# Copy_of_Delay.net
KiCad netlist of a schematic drawn in Altium Designer
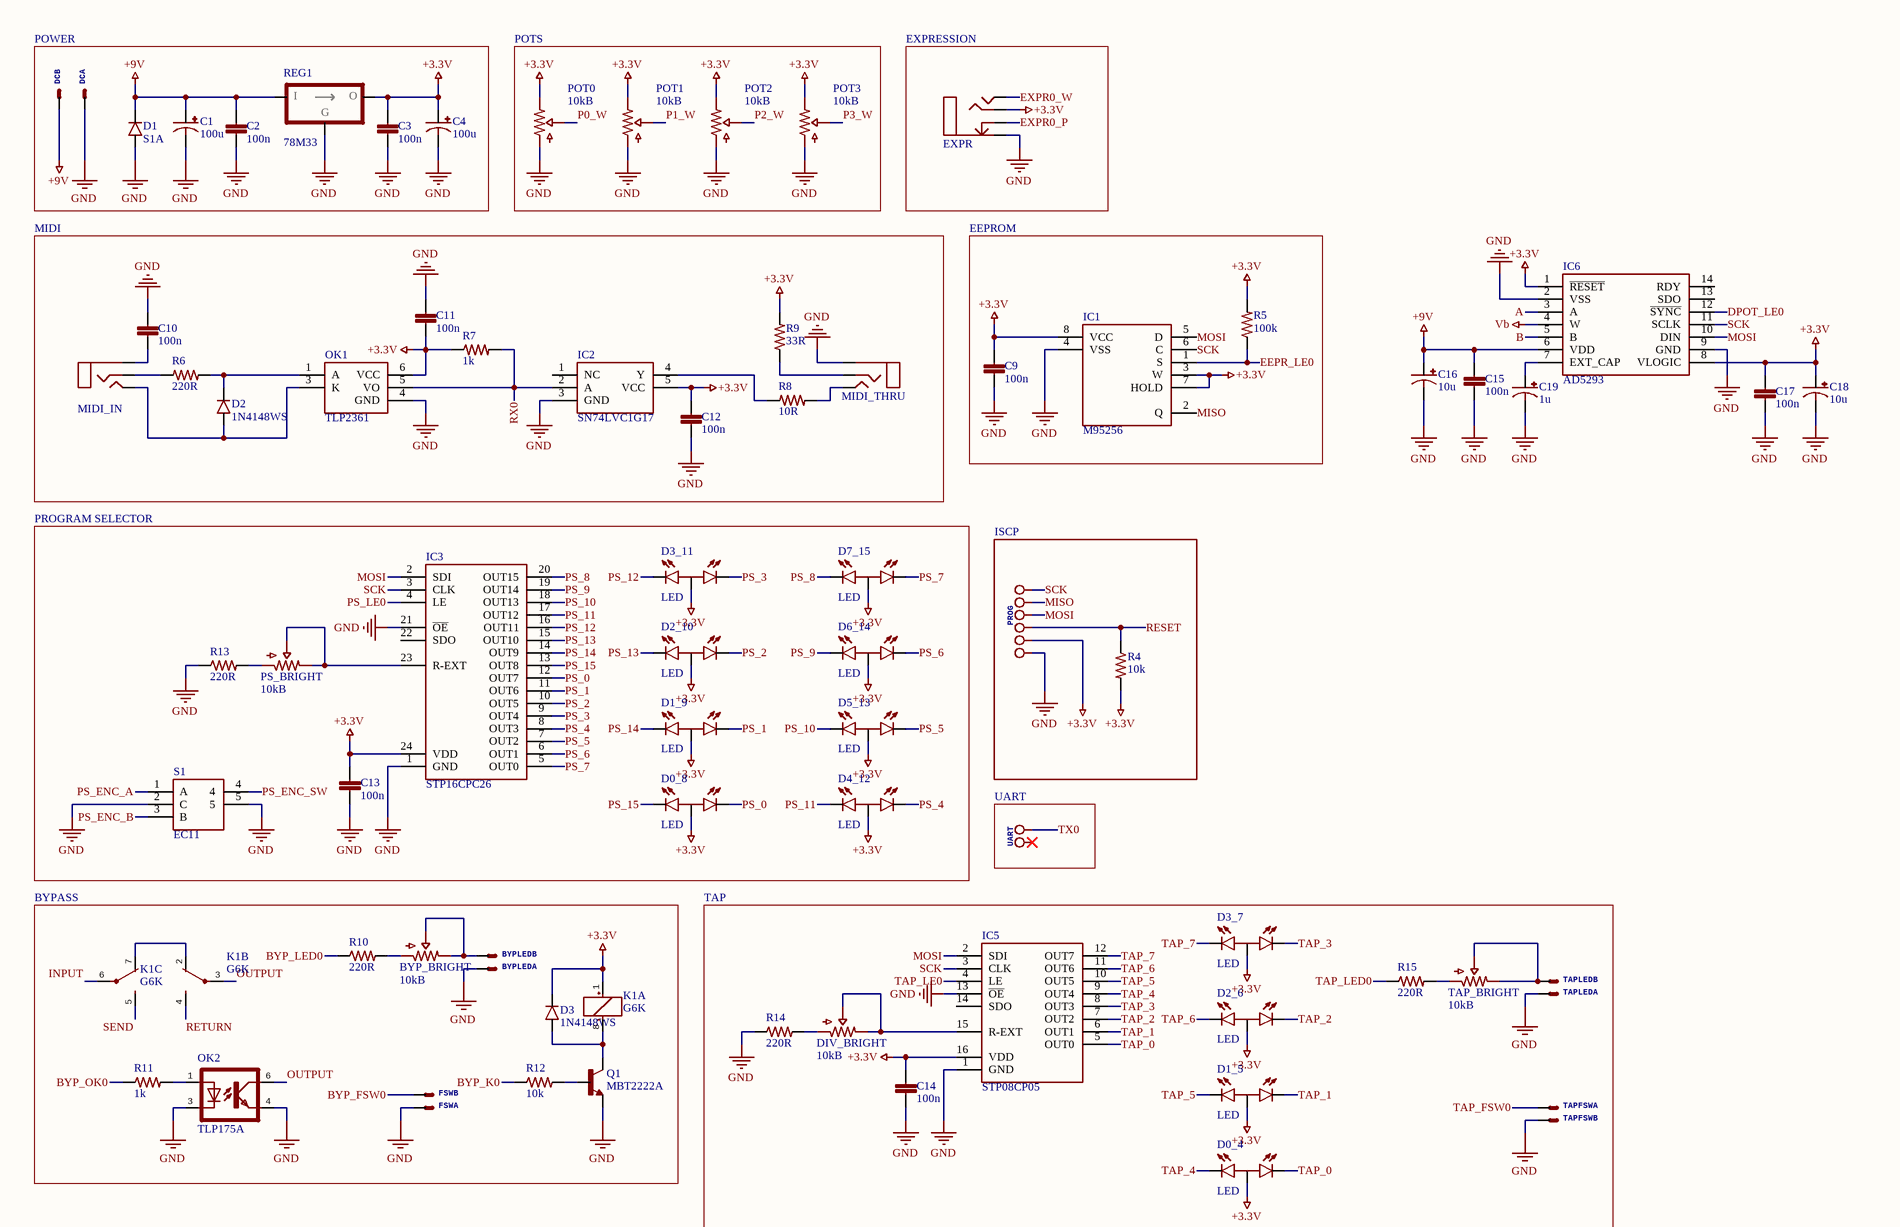
[diagram p0: Copy of Delay.SchDoc, top left]
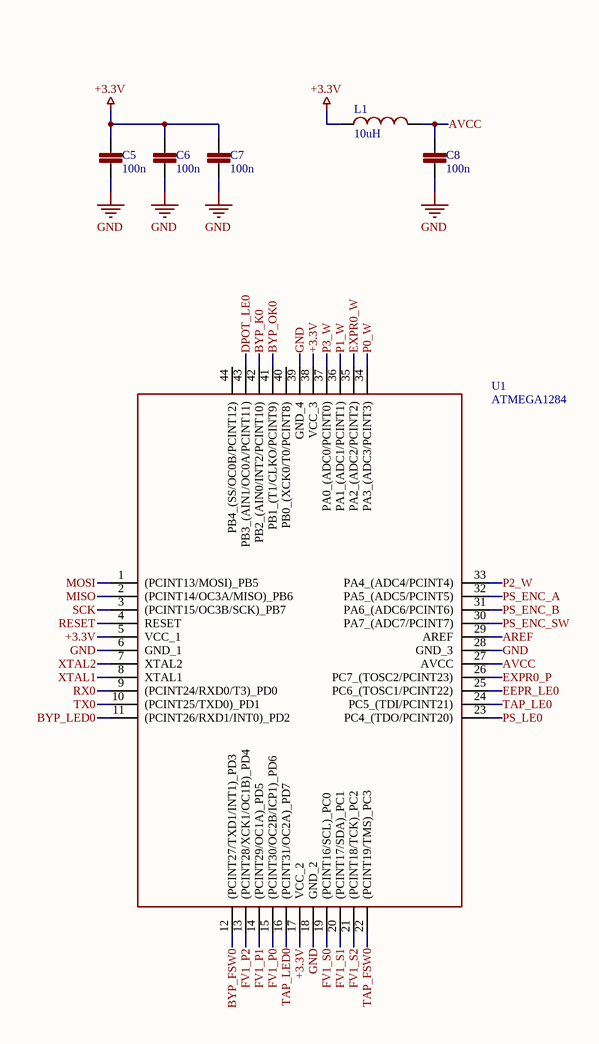
[diagram p1: Copy of Delay.SchDoc, top right]
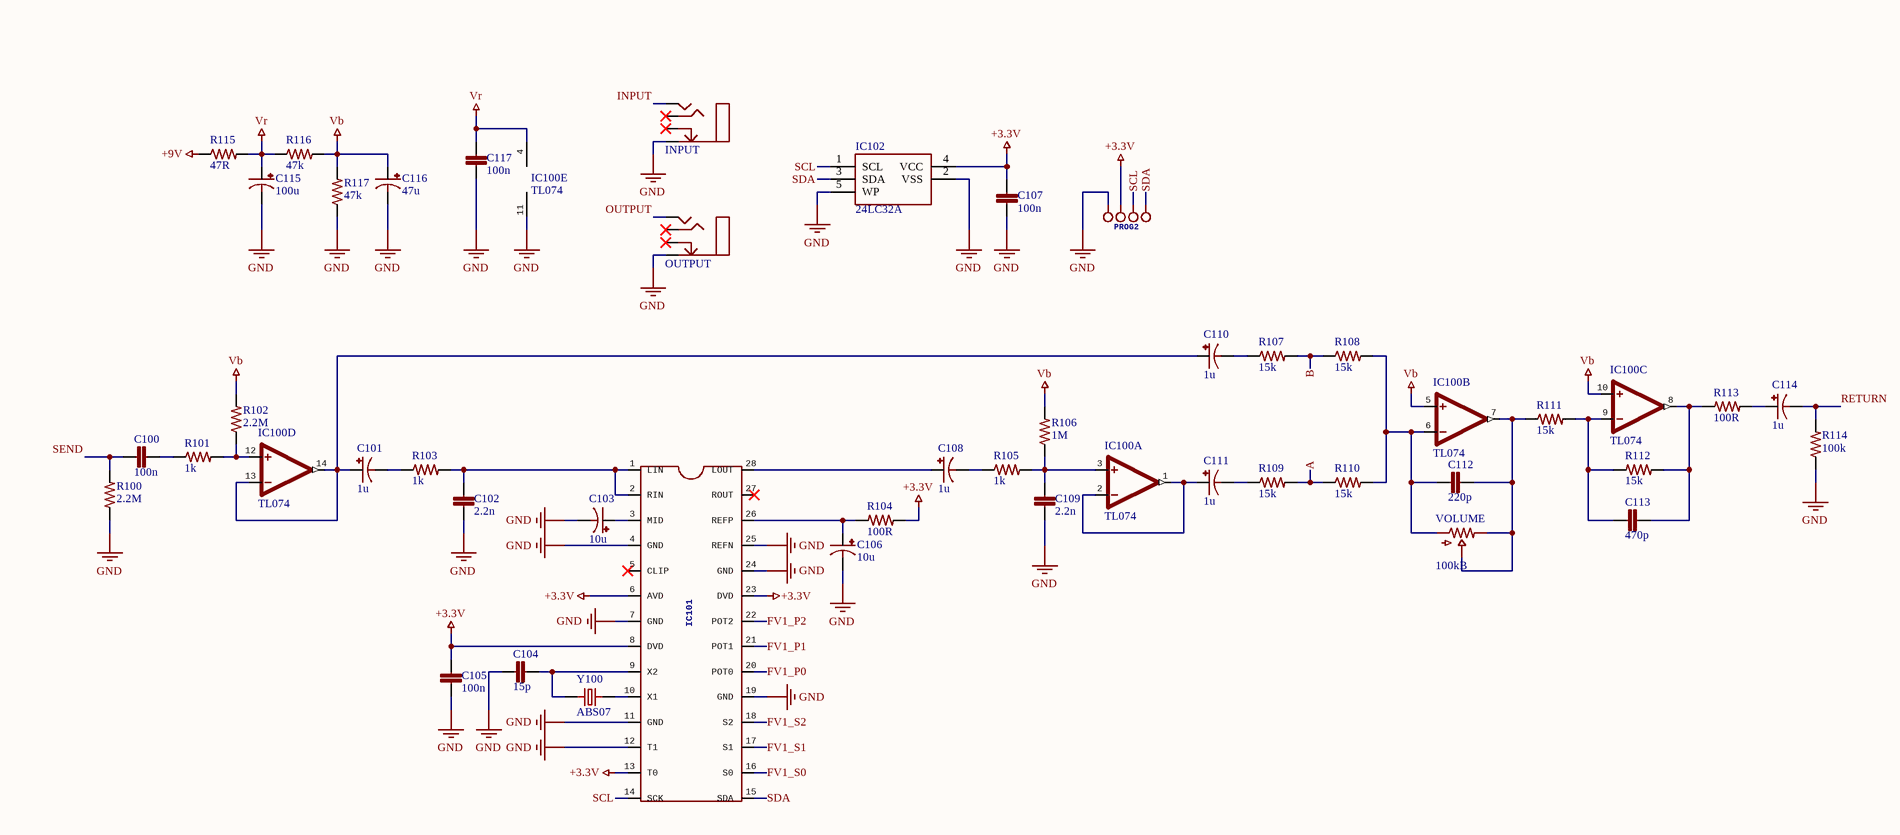
[diagram p2: Copy of Delay.SchDoc, bottom left]

(export (version "E")
  (design (tool "Eeschema 10.0.6"))
  (components
    (comp (ref "BYPLED")
      (value "~")
      (footprint "JST-XH-02")
      (description "2 Pins male XH header")
      (libsource (lib "Pedals") (part "JST-XH-02"))
    )
    (comp (ref "BYP_BRIGHT")
      (value "10kB")
      (footprint "BOURNS_3362P")
      (description "10k Lin 3362P trimmer")
      (libsource (lib "Pedals") (part "TRIM_10kB_3362P"))
    )
    (comp (ref "C1")
      (value "100u")
      (footprint "CAPAE_D")
      (description "CAP ALUM 100UF 25V SMD")
      (fields
        (field (name "MANUFACTURER") "Multicomp")
        (field (name "MANUFACTURER PART NUMBER") "MCVVT025M101EA6L")
      )
      (libsource (lib "Pedals SMD") (part "MCVVT025M101EA6L"))
    )
    (comp (ref "C2")
      (value "100n")
      (footprint "CHIP_0603")
      (description "CAP CER 100NF 50V X7R 0603")
      (fields
        (field (name "MANUFACTURER") "Multicomp")
        (field (name "MANUFACTURER PART NUMBER") "MC0603B104K500CT")
      )
      (libsource (lib "") (part "MC0603B104K500CT_2"))
    )
    (comp (ref "C3")
      (value "100n")
      (footprint "CHIP_0603")
      (description "CAP CER 100NF 50V X7R 0603")
      (fields
        (field (name "MANUFACTURER") "Multicomp")
        (field (name "MANUFACTURER PART NUMBER") "MC0603B104K500CT")
      )
      (libsource (lib "Pedals SMD") (part "MC0603B104K500CT"))
    )
    (comp (ref "C4")
      (value "100u")
      (footprint "CAPAE_D")
      (description "CAP ALUM 100UF 25V SMD")
      (fields
        (field (name "MANUFACTURER") "Multicomp")
        (field (name "MANUFACTURER PART NUMBER") "MCVVT025M101EA6L")
      )
      (libsource (lib "Pedals SMD") (part "MCVVT025M101EA6L"))
    )
    (comp (ref "C5")
      (value "100n")
      (footprint "CHIP_0603")
      (description "CAP CER 100NF 50V X7R 0603")
      (fields
        (field (name "MANUFACTURER") "Multicomp")
        (field (name "MANUFACTURER PART NUMBER") "MC0603B104K500CT")
      )
      (libsource (lib "Pedals SMD") (part "MC0603B104K500CT"))
    )
    (comp (ref "C6")
      (value "100n")
      (footprint "CHIP_0603")
      (description "CAP CER 100NF 50V X7R 0603")
      (fields
        (field (name "MANUFACTURER") "Multicomp")
        (field (name "MANUFACTURER PART NUMBER") "MC0603B104K500CT")
      )
      (libsource (lib "Pedals SMD") (part "MC0603B104K500CT"))
    )
    (comp (ref "C7")
      (value "100n")
      (footprint "CHIP_0603")
      (description "CAP CER 100NF 50V X7R 0603")
      (fields
        (field (name "MANUFACTURER") "Multicomp")
        (field (name "MANUFACTURER PART NUMBER") "MC0603B104K500CT")
      )
      (libsource (lib "Pedals SMD") (part "MC0603B104K500CT"))
    )
    (comp (ref "C8")
      (value "100n")
      (footprint "CHIP_0603")
      (description "CAP CER 100NF 50V X7R 0603")
      (fields
        (field (name "MANUFACTURER") "Multicomp")
        (field (name "MANUFACTURER PART NUMBER") "MC0603B104K500CT")
      )
      (libsource (lib "Pedals SMD") (part "MC0603B104K500CT"))
    )
    (comp (ref "C9")
      (value "100n")
      (footprint "CHIP_0603")
      (description "CAP CER 100NF 50V X7R 0603")
      (fields
        (field (name "MANUFACTURER") "Multicomp")
        (field (name "MANUFACTURER PART NUMBER") "MC0603B104K500CT")
      )
      (libsource (lib "") (part "MC0603B104K500CT_1"))
    )
    (comp (ref "C10")
      (value "100n")
      (footprint "CHIP_0603")
      (description "CAP CER 100NF 50V X7R 0603")
      (fields
        (field (name "MANUFACTURER") "Multicomp")
        (field (name "MANUFACTURER PART NUMBER") "MC0603B104K500CT")
      )
      (libsource (lib "") (part "MC0603B104K500CT_1"))
    )
    (comp (ref "C11")
      (value "100n")
      (footprint "CHIP_0603")
      (description "CAP CER 100NF 50V X7R 0603")
      (fields
        (field (name "MANUFACTURER") "Multicomp")
        (field (name "MANUFACTURER PART NUMBER") "MC0603B104K500CT")
      )
      (libsource (lib "") (part "MC0603B104K500CT_1"))
    )
    (comp (ref "C12")
      (value "100n")
      (footprint "CHIP_0603")
      (description "CAP CER 100NF 50V X7R 0603")
      (fields
        (field (name "MANUFACTURER") "Multicomp")
        (field (name "MANUFACTURER PART NUMBER") "MC0603B104K500CT")
      )
      (libsource (lib "") (part "MC0603B104K500CT_1"))
    )
    (comp (ref "C13")
      (value "100n")
      (footprint "CHIP_0603")
      (description "CAP CER 100NF 50V X7R 0603")
      (fields
        (field (name "MANUFACTURER") "Multicomp")
        (field (name "MANUFACTURER PART NUMBER") "MC0603B104K500CT")
      )
      (libsource (lib "Pedals SMD") (part "MC0603B104K500CT"))
    )
    (comp (ref "C14")
      (value "100n")
      (footprint "CHIP_0603")
      (description "CAP CER 100NF 50V X7R 0603")
      (fields
        (field (name "MANUFACTURER") "Multicomp")
        (field (name "MANUFACTURER PART NUMBER") "MC0603B104K500CT")
      )
      (libsource (lib "Pedals SMD") (part "MC0603B104K500CT"))
    )
    (comp (ref "C15")
      (value "100n")
      (footprint "CHIP_0603")
      (description "CAP CER 100NF 50V X7R 0603")
      (fields
        (field (name "MANUFACTURER") "Multicomp")
        (field (name "MANUFACTURER PART NUMBER") "MC0603B104K500CT")
      )
      (libsource (lib "Pedals SMD") (part "MC0603B104K500CT"))
    )
    (comp (ref "C16")
      (value "10u")
      (footprint "TAN_1206")
      (description "CAP TANT 10UF 16V")
      (fields
        (field (name "MANUFACTURER") "KEMET")
        (field (name "MANUFACTURER PART NUMBER") "T491A106K016AT")
      )
      (libsource (lib "") (part "T491A106K016AT_1"))
    )
    (comp (ref "C17")
      (value "100n")
      (footprint "CHIP_0603")
      (description "CAP CER 100NF 50V X7R 0603")
      (fields
        (field (name "MANUFACTURER") "Multicomp")
        (field (name "MANUFACTURER PART NUMBER") "MC0603B104K500CT")
      )
      (libsource (lib "Pedals SMD") (part "MC0603B104K500CT"))
    )
    (comp (ref "C18")
      (value "10u")
      (footprint "TAN_1206")
      (description "CAP TANT 10UF 16V")
      (fields
        (field (name "MANUFACTURER") "KEMET")
        (field (name "MANUFACTURER PART NUMBER") "T491A106K016AT")
      )
      (libsource (lib "") (part "T491A106K016AT_1"))
    )
    (comp (ref "C19")
      (value "1u")
      (footprint "TAN_1206")
      (description "CAP TANT 1UF 16V")
      (fields
        (field (name "MANUFACTURER") "KEMET")
        (field (name "MANUFACTURER PART NUMBER") "T491A105K016AT")
      )
      (libsource (lib "Pedals SMD") (part "T491A105K016AT"))
    )
    (comp (ref "C100")
      (value "100n")
      (footprint "CHIP_1206")
      (description "CAP CER 100NF 50V C0G/NP0 1206")
      (fields
        (field (name "MANUFACTURER") "Murata")
        (field (name "MANUFACTURER PART NUMBER") "GRM31C5C1H104JA01L")
      )
      (libsource (lib "Pedals SMD") (part "GRM31C5C1H104JA01L"))
    )
    (comp (ref "C101")
      (value "1u")
      (footprint "CAPAE_B")
      (description "CAP ALUM 1UF 50V LESR SMD")
      (fields
        (field (name "MANUFACTURER") "Panasonic")
        (field (name "MANUFACTURER PART NUMBER") "EEEFC1H1R0R")
      )
      (libsource (lib "Pedals SMD") (part "EEEFC1H1R0R"))
    )
    (comp (ref "C102")
      (value "2.2n")
      (footprint "CHIP_0603")
      (description "CAP CER 2.2NF 50V C0G/NP0 0603")
      (fields
        (field (name "MANUFACTURER") "Murata")
        (field (name "MANUFACTURER PART NUMBER") "GRM1885C1H222JA01D")
      )
      (libsource (lib "Pedals SMD") (part "GRM1885C1H222JA01D"))
    )
    (comp (ref "C103")
      (value "10u")
      (footprint "TAN_1206")
      (description "CAP TANT 10UF 16V")
      (fields
        (field (name "MANUFACTURER") "KEMET")
        (field (name "MANUFACTURER PART NUMBER") "T491A106K016AT")
      )
      (libsource (lib "Pedals SMD") (part "T491A106K016AT"))
    )
    (comp (ref "C104")
      (value "15p")
      (footprint "CHIP_0603")
      (description "CAP CER 15PF 50V C0G/NP0 0603")
      (fields
        (field (name "MANUFACTURER") "Multicomp")
        (field (name "MANUFACTURER PART NUMBER") "MC0603N150J500CT")
      )
      (libsource (lib "Pedals SMD") (part "MC0603N150J500CT"))
    )
    (comp (ref "C105")
      (value "100n")
      (footprint "CHIP_0603")
      (description "CAP CER 100NF 50V X7R 0603")
      (fields
        (field (name "MANUFACTURER") "Multicomp")
        (field (name "MANUFACTURER PART NUMBER") "MC0603B104K500CT")
      )
      (libsource (lib "Pedals SMD") (part "MC0603B104K500CT"))
    )
    (comp (ref "C106")
      (value "10u")
      (footprint "TAN_1206")
      (description "CAP TANT 10UF 16V")
      (fields
        (field (name "MANUFACTURER") "KEMET")
        (field (name "MANUFACTURER PART NUMBER") "T491A106K016AT")
      )
      (libsource (lib "") (part "T491A106K016AT_1"))
    )
    (comp (ref "C107")
      (value "100n")
      (footprint "CHIP_0603")
      (description "CAP CER 100NF 50V X7R 0603")
      (fields
        (field (name "MANUFACTURER") "Multicomp")
        (field (name "MANUFACTURER PART NUMBER") "MC0603B104K500CT")
      )
      (libsource (lib "Pedals SMD") (part "MC0603B104K500CT"))
    )
    (comp (ref "C108")
      (value "1u")
      (footprint "CAPAE_B")
      (description "CAP ALUM 1UF 50V LESR SMD")
      (fields
        (field (name "MANUFACTURER") "Panasonic")
        (field (name "MANUFACTURER PART NUMBER") "EEEFC1H1R0R")
      )
      (libsource (lib "Pedals SMD") (part "EEEFC1H1R0R"))
    )
    (comp (ref "C109")
      (value "2.2n")
      (footprint "CHIP_0603")
      (description "CAP CER 2.2NF 50V C0G/NP0 0603")
      (fields
        (field (name "MANUFACTURER") "Murata")
        (field (name "MANUFACTURER PART NUMBER") "GRM1885C1H222JA01D")
      )
      (libsource (lib "Pedals SMD") (part "GRM1885C1H222JA01D"))
    )
    (comp (ref "C110")
      (value "1u")
      (footprint "CAPAE_B")
      (description "CAP ALUM 1UF 50V LESR SMD")
      (fields
        (field (name "MANUFACTURER") "Panasonic")
        (field (name "MANUFACTURER PART NUMBER") "EEEFC1H1R0R")
      )
      (libsource (lib "Pedals SMD") (part "EEEFC1H1R0R"))
    )
    (comp (ref "C111")
      (value "1u")
      (footprint "CAPAE_B")
      (description "CAP ALUM 1UF 50V LESR SMD")
      (fields
        (field (name "MANUFACTURER") "Panasonic")
        (field (name "MANUFACTURER PART NUMBER") "EEEFC1H1R0R")
      )
      (libsource (lib "Pedals SMD") (part "EEEFC1H1R0R"))
    )
    (comp (ref "C112")
      (value "220p")
      (footprint "CHIP_0603")
      (description "CAP CER 220PF 50V C0G/NP0 0603")
      (fields
        (field (name "MANUFACTURER") "Multicomp")
        (field (name "MANUFACTURER PART NUMBER") "MC0603N221J500CT")
      )
      (libsource (lib "Pedals SMD") (part "MC0603N221J500CT"))
    )
    (comp (ref "C113")
      (value "470p")
      (footprint "CHIP_0603")
      (description "CAP CER 470PF 50V C0G/NP0 0603")
      (fields
        (field (name "MANUFACTURER") "Multicomp")
        (field (name "MANUFACTURER PART NUMBER") "MC0603N471J500CT")
      )
      (libsource (lib "Pedals SMD") (part "MC0603N471J500CT"))
    )
    (comp (ref "C114")
      (value "1u")
      (footprint "CAPAE_B")
      (description "CAP ALUM 1UF 50V LESR SMD")
      (fields
        (field (name "MANUFACTURER") "Panasonic")
        (field (name "MANUFACTURER PART NUMBER") "EEEFC1H1R0R")
      )
      (libsource (lib "Pedals SMD") (part "EEEFC1H1R0R"))
    )
    (comp (ref "C115")
      (value "100u")
      (footprint "CAPAE_D")
      (description "CAP ALUM 100UF 25V SMD")
      (fields
        (field (name "MANUFACTURER") "Multicomp")
        (field (name "MANUFACTURER PART NUMBER") "MCVVT025M101EA6L")
      )
      (libsource (lib "Pedals SMD") (part "MCVVT025M101EA6L"))
    )
    (comp (ref "C116")
      (value "47u")
      (footprint "CAPAE_D")
      (description "CAP ALUM 47UF 25V SMD")
      (fields
        (field (name "MANUFACTURER") "Multicomp")
        (field (name "MANUFACTURER PART NUMBER") "MCVVT025M470EA1L")
      )
      (libsource (lib "Pedals SMD") (part "MCVVT025M470EA1L"))
    )
    (comp (ref "C117")
      (value "100n")
      (footprint "CHIP_0603")
      (description "CAP CER 100NF 50V X7R 0603")
      (fields
        (field (name "MANUFACTURER") "Multicomp")
        (field (name "MANUFACTURER PART NUMBER") "MC0603B104K500CT")
      )
      (libsource (lib "Pedals SMD") (part "MC0603B104K500CT"))
    )
    (comp (ref "D0_4")
      (value "LED")
      (footprint "LED_3MM_BICOLOR")
      (description "BICOLOR LED")
      (libsource (lib "Pedals") (part "D_BICOLOR_LED"))
    )
    (comp (ref "D0_8")
      (value "LED")
      (footprint "LED_3MM_BICOLOR")
      (description "BICOLOR LED")
      (libsource (lib "Pedals") (part "D_BICOLOR_LED"))
    )
    (comp (ref "D1")
      (value "S1A")
      (footprint "DO214")
      (description "DIODE GEN PURP 50V 1A SMA")
      (fields (field (name "MANUFACTURER") "ON Semiconductor / Fairchild"))
      (libsource (lib "Pedals SMD") (part "S1A"))
    )
    (comp (ref "D1_5")
      (value "LED")
      (footprint "LED_3MM_BICOLOR")
      (description "BICOLOR LED")
      (libsource (lib "Pedals") (part "D_BICOLOR_LED"))
    )
    (comp (ref "D1_9")
      (value "LED")
      (footprint "LED_3MM_BICOLOR")
      (description "BICOLOR LED")
      (libsource (lib "Pedals") (part "D_BICOLOR_LED"))
    )
    (comp (ref "D2")
      (value "1N4148WS")
      (footprint "SOD323")
      (description "DIODE GEN PURP 75V 150MA SOD323F")
      (fields (field (name "MANUFACTURER") "ON Semiconductor / Fairchild"))
      (libsource (lib "Pedals SMD") (part "1N4148WS"))
    )
    (comp (ref "D2_6")
      (value "LED")
      (footprint "LED_3MM_BICOLOR")
      (description "BICOLOR LED")
      (libsource (lib "Pedals") (part "D_BICOLOR_LED"))
    )
    (comp (ref "D2_10")
      (value "LED")
      (footprint "LED_3MM_BICOLOR")
      (description "BICOLOR LED")
      (libsource (lib "Pedals") (part "D_BICOLOR_LED"))
    )
    (comp (ref "D3")
      (value "1N4148WS")
      (footprint "SOD323")
      (description "DIODE GEN PURP 75V 150MA SOD323F")
      (fields (field (name "MANUFACTURER") "ON Semiconductor / Fairchild"))
      (libsource (lib "Pedals SMD") (part "1N4148WS"))
    )
    (comp (ref "D3_7")
      (value "LED")
      (footprint "LED_3MM_BICOLOR")
      (description "BICOLOR LED")
      (libsource (lib "Pedals") (part "D_BICOLOR_LED"))
    )
    (comp (ref "D3_11")
      (value "LED")
      (footprint "LED_3MM_BICOLOR")
      (description "BICOLOR LED")
      (libsource (lib "Pedals") (part "D_BICOLOR_LED"))
    )
    (comp (ref "D4_12")
      (value "LED")
      (footprint "LED_3MM_BICOLOR")
      (description "BICOLOR LED")
      (libsource (lib "Pedals") (part "D_BICOLOR_LED"))
    )
    (comp (ref "D5_13")
      (value "LED")
      (footprint "LED_3MM_BICOLOR")
      (description "BICOLOR LED")
      (libsource (lib "Pedals") (part "D_BICOLOR_LED"))
    )
    (comp (ref "D6_14")
      (value "LED")
      (footprint "LED_3MM_BICOLOR")
      (description "BICOLOR LED")
      (libsource (lib "Pedals") (part "D_BICOLOR_LED"))
    )
    (comp (ref "D7_15")
      (value "LED")
      (footprint "LED_3MM_BICOLOR")
      (description "BICOLOR LED")
      (libsource (lib "Pedals") (part "D_BICOLOR_LED"))
    )
    (comp (ref "DC")
      (value "J_JST-XH-02")
      (footprint "JST-XH-02")
      (description "2 Pins male XH header")
      (libsource (lib "Pedals") (part "J_JST-XH-02"))
    )
    (comp (ref "DIV_BRIGHT")
      (value "10kB")
      (footprint "BOURNS_3362P")
      (description "10k Lin 3362P trimmer")
      (libsource (lib "Pedals") (part "TRIM_10kB_3362P"))
    )
    (comp (ref "EXPR")
      (value "J_STEREO")
      (footprint "STEREO")
      (description "6.35mm stereo insulated socket jack PCB mounted")
      (libsource (lib "Pedals") (part "J_STEREO"))
    )
    (comp (ref "FSW")
      (value "~")
      (footprint "JST-XH-02")
      (description "2 Pins male XH header")
      (libsource (lib "Pedals") (part "JST-XH-02"))
    )
    (comp (ref "IC1")
      (value "M95256")
      (footprint "SO-8")
      (description "IC EEPROM 256K SPI 20MHZ 8SO")
      (fields
        (field (name "MANUFACTURER") "STMicroelectronics")
        (field (name "MANUFACTURER PART NUMBER") "M95256-WMN6P")
      )
      (libsource (lib "Pedals SMD") (part "M95256-WMN6P"))
    )
    (comp (ref "IC2")
      (value "SN74LVC1G17")
      (footprint "SOT-23-5")
      (description "Schmitt Trigger Buffer 1-CH Non-Inverting CMOS Automotive 5-Pin SOT-23 T/R")
      (fields
        (field (name "MANUFACTURER") "Texas Instruments")
        (field (name "MANUFACTURER PART NUMBER") "SN74LVC1G17QDBVRQ1")
      )
      (libsource (lib "Pedals SMD") (part "SN74LVC1G17QDBVRQ1"))
    )
    (comp (ref "IC3")
      (value "STP16CPC26")
      (footprint "SO-24")
      (description "IC LED DRIVER LIN DIM 90MA 24SO")
      (fields
        (field (name "MANUFACTURER") "STMicroelectronics")
        (field (name "MANUFACTURER PART NUMBER") "STP16CPC26MTR")
      )
      (libsource (lib "Pedals SMD") (part "STP16CPC26MTR"))
    )
    (comp (ref "IC5")
      (value "STP08CP05")
      (footprint "SO-16")
      (description "IC SHIFT REGISTER 8BIT 16SOIC")
      (fields
        (field (name "MANUFACTURER") "STMicroelectronics")
        (field (name "MANUFACTURER PART NUMBER") "STP08CP05MTR")
      )
      (libsource (lib "Pedals SMD") (part "STP08CP05MTR"))
    )
    (comp (ref "IC6")
      (value "AD5293")
      (footprint "TSSOP-14")
      (description "Digital Potentiometer 20kOhm 1024POS Volatile 14-Pin TSSOP Tube")
      (fields
        (field (name "MANUFACTURER") "Analog Devices")
        (field (name "MANUFACTURER PART NUMBER") "AD5293BRUZ-20")
      )
      (libsource (lib "Pedals SMD") (part "AD5293BRUZ-20"))
    )
    (comp (ref "IC100")
      (value "TL074")
      (footprint "SO-14")
      (description "IC OPAMP JFET 3MHZ 14SO")
      (fields
        (field (name "MANUFACTURER") "STMicroelectronics")
        (field (name "MANUFACTURER PART NUMBER") "TL074IDT")
      )
      (libsource (lib "Pedals SMD") (part "TL074IDT"))
    )
    (comp (ref "IC101")
      (value "FV-1")
      (footprint "SO-28")
      (description "Spinsemi FV-1")
      (libsource (lib "Pedals SMD") (part "FV-1"))
    )
    (comp (ref "IC102")
      (value "24LC32A")
      (footprint "SOT-23-5")
      (description "IC EEPROM 32KBIT 400KHZ SOT23-5")
      (fields
        (field (name "MANUFACTURER") "Microchip")
        (field (name "MANUFACTURER PART NUMBER") "24LC32AT-I/OT")
      )
      (libsource (lib "Pedals SMD") (part "24LC32AT-I/OT"))
    )
    (comp (ref "INPUT")
      (value "J_STEREO")
      (footprint "STEREO")
      (description "6.35mm stereo insulated socket jack PCB mounted")
      (libsource (lib "Pedals") (part "J_STEREO"))
    )
    (comp (ref "K1")
      (value "G6K")
      (footprint "G6K")
      (description "OMRON ELECTRONIC COMPONENTS   G6K-2F 3DC   RELAY, SMD, DPCO, 3VDC")
      (fields (field (name "MANUFACTURER") "Omron") (field (name "MANUFACTURER PART NUMBER") "G6K2F3DC"))
      (libsource (lib "") (part "G6K2F3DC_2"))
    )
    (comp (ref "L1")
      (value "10uH")
      (footprint "INDC1608X10")
      (fields
        (field (name "MANUFACTURER") "TDK")
        (field (name "MANUFACTURER PART NUMBER") "MLZ1608N100LT")
        (field (name "TOLERANCE") "20%")
      )
      (libsource (lib "Pedals SMD") (part "MLZ1608N100LT"))
    )
    (comp (ref "MIDI_IN")
      (value "J_STEREO_3.5")
      (footprint "STEREO_3.5")
      (description "3.5mm stereo socket jack PCB mounted")
      (libsource (lib "Pedals") (part "J_STEREO_3.5"))
    )
    (comp (ref "MIDI_THRU")
      (value "J_STEREO_3.5")
      (footprint "STEREO_3.5")
      (description "3.5mm stereo socket jack PCB mounted")
      (libsource (lib "Pedals") (part "J_STEREO_3.5"))
    )
    (comp (ref "OK1")
      (value "TLP2361")
      (footprint "TLP2361")
      (description "TOSHIBA - TLP2361 - OPTOKOPPLER, DIGITAL, 3.75KV, SOP-5")
      (fields (field (name "MANUFACTURER") "Toshiba"))
      (libsource (lib "Pedals SMD") (part "TLP2361"))
    )
    (comp (ref "OK2")
      (value "TLP175A")
      (footprint "TLP175A")
      (description "Toshiba TLP175A AC Input MOSFET Output Optocoupler, Surface Mount, 4-Pin SOIC")
      (fields (field (name "MANUFACTURER") "Toshiba"))
      (libsource (lib "Pedals SMD") (part "TLP175A"))
    )
    (comp (ref "OUTPUT")
      (value "J_STEREO")
      (footprint "STEREO")
      (description "6.35mm stereo insulated socket jack PCB mounted")
      (libsource (lib "Pedals") (part "J_STEREO"))
    )
    (comp (ref "POT0")
      (value "10kB")
      (footprint "ALPHA_9MM_TOP_NOMH")
      (description "10k Lin potentiometer round shaft")
      (libsource (lib "Pedals") (part "POT_10kB_ALPHA_9mm"))
    )
    (comp (ref "POT1")
      (value "10kB")
      (footprint "ALPHA_9MM_TOP_NOMH")
      (description "10k Lin potentiometer round shaft")
      (libsource (lib "Pedals") (part "POT_10kB_ALPHA_9mm"))
    )
    (comp (ref "POT2")
      (value "10kB")
      (footprint "ALPHA_9MM_TOP_NOMH")
      (description "10k Lin potentiometer round shaft")
      (libsource (lib "Pedals") (part "POT_10kB_ALPHA_9mm"))
    )
    (comp (ref "POT3")
      (value "10kB")
      (footprint "ALPHA_9MM_TOP_NOMH")
      (description "10k Lin potentiometer round shaft")
      (libsource (lib "Pedals") (part "POT_10kB_ALPHA_9mm"))
    )
    (comp (ref "PROG")
      (value "J_HEADER_6PINS_FEM")
      (footprint "HEADER_6Pins_FEM")
      (description "5 Pins female header")
      (libsource (lib "Pedals") (part "J_HEADER_6PINS_FEM"))
    )
    (comp (ref "PROG2")
      (value "J_HEADER_4PINS_FEM")
      (footprint "HEADER_4Pins_FEM")
      (description "4 Pins female header")
      (libsource (lib "Pedals") (part "J_HEADER_4PINS_FEM"))
    )
    (comp (ref "PS_BRIGHT")
      (value "10kB")
      (footprint "BOURNS_3362P")
      (description "10k Lin 3362P trimmer")
      (libsource (lib "Pedals") (part "TRIM_10kB_3362P"))
    )
    (comp (ref "Q1")
      (value "MBT2222A")
      (footprint "SOT323")
      (description "TRANS NPN 40V 0.6A SOT323")
      (fields
        (field (name "MANUFACTURER") "ON Semiconductor")
        (field (name "MANUFACTURER PART NUMBER") "MMBT2222AWT1G")
      )
      (libsource (lib "Pedals SMD") (part "MMBT2222AWT1G"))
    )
    (comp (ref "R4")
      (value "10k")
      (footprint "CHIP_R_0603")
      (description "RES SMD 10K OHM 1% 1/10W 0603")
      (fields
        (field (name "MANUFACTURER") "Vishay")
        (field (name "MANUFACTURER PART NUMBER") "CRCW060310K0FKEA")
      )
      (libsource (lib "Pedals SMD") (part "CRCW060310K0FKEA"))
    )
    (comp (ref "R5")
      (value "100k")
      (footprint "CHIP_R_0603")
      (description "RES SMD 100K OHM 1% 1/10W 0603")
      (fields
        (field (name "MANUFACTURER") "Vishay")
        (field (name "MANUFACTURER PART NUMBER") "CRCW0603100KFKEA")
      )
      (libsource (lib "Pedals SMD") (part "CRCW0603100KFKEA"))
    )
    (comp (ref "R6")
      (value "220R")
      (footprint "CHIP_R_0603")
      (description "RES SMD 220 OHM 1% 1/10W 0603")
      (fields
        (field (name "MANUFACTURER") "Vishay")
        (field (name "MANUFACTURER PART NUMBER") "CRCW0603220RFKEA")
      )
      (libsource (lib "Pedals SMD") (part "CRCW0603220RFKEA"))
    )
    (comp (ref "R7")
      (value "1k")
      (footprint "CHIP_R_0603")
      (description "RES SMD 1K OHM 1% 1/10W 0603")
      (fields
        (field (name "MANUFACTURER") "Vishay Dale")
        (field (name "MANUFACTURER PART NUMBER") "CRCW06031K00FKEA")
      )
      (libsource (lib "Pedals SMD") (part "CRCW06031K00FKEA"))
    )
    (comp (ref "R8")
      (value "10R")
      (footprint "CHIP_R_0603")
      (description "RES SMD 10 OHM 1% 1/10W 0603")
      (fields
        (field (name "MANUFACTURER") "Vishay")
        (field (name "MANUFACTURER PART NUMBER") "CRCW060310R0FKEA")
      )
      (libsource (lib "Pedals SMD") (part "CRCW060310R0FKEA"))
    )
    (comp (ref "R9")
      (value "33R")
      (footprint "CHIP_R_0603")
      (description "RES SMD 33 OHM 1% 1/10W 0603")
      (fields
        (field (name "MANUFACTURER") "Vishay")
        (field (name "MANUFACTURER PART NUMBER") "CRCW060333R0FKEA")
      )
      (libsource (lib "Pedals SMD") (part "CRCW060333R0FKEA"))
    )
    (comp (ref "R10")
      (value "220R")
      (footprint "CHIP_R_1206")
      (description "RES SMD 220 OHM 1% 1/4W 1206")
      (fields
        (field (name "MANUFACTURER") "Vishay")
        (field (name "MANUFACTURER PART NUMBER") "CRCW1206220RFKEA")
      )
      (libsource (lib "Pedals SMD") (part "CRCW1206220RFKEA"))
    )
    (comp (ref "R11")
      (value "1k")
      (footprint "CHIP_R_0603")
      (description "RES SMD 1K OHM 1% 1/10W 0603")
      (fields
        (field (name "MANUFACTURER") "Vishay Dale")
        (field (name "MANUFACTURER PART NUMBER") "CRCW06031K00FKEA")
      )
      (libsource (lib "Pedals SMD") (part "CRCW06031K00FKEA"))
    )
    (comp (ref "R12")
      (value "10k")
      (footprint "CHIP_R_0603")
      (description "RES SMD 10K OHM 1% 1/10W 0603")
      (fields
        (field (name "MANUFACTURER") "Vishay")
        (field (name "MANUFACTURER PART NUMBER") "CRCW060310K0FKEA")
      )
      (libsource (lib "Pedals SMD") (part "CRCW060310K0FKEA"))
    )
    (comp (ref "R13")
      (value "220R")
      (footprint "CHIP_R_1206")
      (description "RES SMD 220 OHM 1% 1/4W 1206")
      (fields
        (field (name "MANUFACTURER") "Vishay")
        (field (name "MANUFACTURER PART NUMBER") "CRCW1206220RFKEA")
      )
      (libsource (lib "Pedals SMD") (part "CRCW1206220RFKEA"))
    )
    (comp (ref "R14")
      (value "220R")
      (footprint "CHIP_R_1206")
      (description "RES SMD 220 OHM 1% 1/4W 1206")
      (fields
        (field (name "MANUFACTURER") "Vishay")
        (field (name "MANUFACTURER PART NUMBER") "CRCW1206220RFKEA")
      )
      (libsource (lib "Pedals SMD") (part "CRCW1206220RFKEA"))
    )
    (comp (ref "R15")
      (value "220R")
      (footprint "CHIP_R_1206")
      (description "RES SMD 220 OHM 1% 1/4W 1206")
      (fields
        (field (name "MANUFACTURER") "Vishay")
        (field (name "MANUFACTURER PART NUMBER") "CRCW1206220RFKEA")
      )
      (libsource (lib "Pedals SMD") (part "CRCW1206220RFKEA"))
    )
    (comp (ref "R100")
      (value "2.2M")
      (footprint "CHIP_R_0603")
      (description "RES SMD 2.2M OHM 1% 1/10W 0603")
      (fields
        (field (name "MANUFACTURER") "Vishay")
        (field (name "MANUFACTURER PART NUMBER") "CRCW06032M20FKEA")
      )
      (libsource (lib "Pedals SMD") (part "CRCW06032M20FKEA"))
    )
    (comp (ref "R101")
      (value "1k")
      (footprint "CHIP_R_0603")
      (description "RES SMD 1K OHM 1% 1/10W 0603")
      (fields
        (field (name "MANUFACTURER") "Vishay Dale")
        (field (name "MANUFACTURER PART NUMBER") "CRCW06031K00FKEA")
      )
      (libsource (lib "Pedals SMD") (part "CRCW06031K00FKEA"))
    )
    (comp (ref "R102")
      (value "2.2M")
      (footprint "CHIP_R_0603")
      (description "RES SMD 2.2M OHM 1% 1/10W 0603")
      (fields
        (field (name "MANUFACTURER") "Vishay")
        (field (name "MANUFACTURER PART NUMBER") "CRCW06032M20FKEA")
      )
      (libsource (lib "Pedals SMD") (part "CRCW06032M20FKEA"))
    )
    (comp (ref "R103")
      (value "1k")
      (footprint "CHIP_R_0603")
      (description "RES SMD 1K OHM 1% 1/10W 0603")
      (fields
        (field (name "MANUFACTURER") "Vishay Dale")
        (field (name "MANUFACTURER PART NUMBER") "CRCW06031K00FKEA")
      )
      (libsource (lib "Pedals SMD") (part "CRCW06031K00FKEA"))
    )
    (comp (ref "R104")
      (value "100R")
      (footprint "CHIP_R_0603")
      (description "RES SMD 100 OHM 1% 1/10W 0603")
      (fields
        (field (name "MANUFACTURER") "Vishay Dale")
        (field (name "MANUFACTURER PART NUMBER") "CRCW0603100RFKEA")
      )
      (libsource (lib "Pedals SMD") (part "CRCW0603100RFKEA"))
    )
    (comp (ref "R105")
      (value "1k")
      (footprint "CHIP_R_0603")
      (description "RES SMD 1K OHM 1% 1/10W 0603")
      (fields
        (field (name "MANUFACTURER") "Vishay Dale")
        (field (name "MANUFACTURER PART NUMBER") "CRCW06031K00FKEA")
      )
      (libsource (lib "Pedals SMD") (part "CRCW06031K00FKEA"))
    )
    (comp (ref "R106")
      (value "1M")
      (footprint "CHIP_R_0603")
      (description "RES SMD 1M OHM 1% 1/10W 0603")
      (fields
        (field (name "MANUFACTURER") "Vishay")
        (field (name "MANUFACTURER PART NUMBER") "CRCW06031M00FKEA")
      )
      (libsource (lib "Pedals SMD") (part "CRCW06031M00FKEA"))
    )
    (comp (ref "R107")
      (value "15k")
      (footprint "CHIP_R_0603")
      (description "RES SMD 15K OHM 1% 1/10W 0603")
      (fields
        (field (name "MANUFACTURER") "Vishay")
        (field (name "MANUFACTURER PART NUMBER") "CRCW060315K0FKEA")
      )
      (libsource (lib "Pedals SMD") (part "CRCW060315K0FKEA"))
    )
    (comp (ref "R108")
      (value "15k")
      (footprint "CHIP_R_0603")
      (description "RES SMD 15K OHM 1% 1/10W 0603")
      (fields
        (field (name "MANUFACTURER") "Vishay")
        (field (name "MANUFACTURER PART NUMBER") "CRCW060315K0FKEA")
      )
      (libsource (lib "Pedals SMD") (part "CRCW060315K0FKEA"))
    )
    (comp (ref "R109")
      (value "15k")
      (footprint "CHIP_R_0603")
      (description "RES SMD 15K OHM 1% 1/10W 0603")
      (fields
        (field (name "MANUFACTURER") "Vishay")
        (field (name "MANUFACTURER PART NUMBER") "CRCW060315K0FKEA")
      )
      (libsource (lib "Pedals SMD") (part "CRCW060315K0FKEA"))
    )
    (comp (ref "R110")
      (value "15k")
      (footprint "CHIP_R_0603")
      (description "RES SMD 15K OHM 1% 1/10W 0603")
      (fields
        (field (name "MANUFACTURER") "Vishay")
        (field (name "MANUFACTURER PART NUMBER") "CRCW060315K0FKEA")
      )
      (libsource (lib "Pedals SMD") (part "CRCW060315K0FKEA"))
    )
    (comp (ref "R111")
      (value "15k")
      (footprint "CHIP_R_0603")
      (description "RES SMD 15K OHM 1% 1/10W 0603")
      (fields
        (field (name "MANUFACTURER") "Vishay")
        (field (name "MANUFACTURER PART NUMBER") "CRCW060315K0FKEA")
      )
      (libsource (lib "Pedals SMD") (part "CRCW060315K0FKEA"))
    )
    (comp (ref "R112")
      (value "15k")
      (footprint "CHIP_R_0603")
      (description "RES SMD 15K OHM 1% 1/10W 0603")
      (fields
        (field (name "MANUFACTURER") "Vishay")
        (field (name "MANUFACTURER PART NUMBER") "CRCW060315K0FKEA")
      )
      (libsource (lib "Pedals SMD") (part "CRCW060315K0FKEA"))
    )
    (comp (ref "R113")
      (value "100R")
      (footprint "CHIP_R_0603")
      (description "RES SMD 100 OHM 1% 1/10W 0603")
      (fields
        (field (name "MANUFACTURER") "Vishay Dale")
        (field (name "MANUFACTURER PART NUMBER") "CRCW0603100RFKEA")
      )
      (libsource (lib "Pedals SMD") (part "CRCW0603100RFKEA"))
    )
    (comp (ref "R114")
      (value "100k")
      (footprint "CHIP_R_0603")
      (description "RES SMD 100K OHM 1% 1/10W 0603")
      (fields
        (field (name "MANUFACTURER") "Vishay")
        (field (name "MANUFACTURER PART NUMBER") "CRCW0603100KFKEA")
      )
      (libsource (lib "Pedals SMD") (part "CRCW0603100KFKEA"))
    )
    (comp (ref "R115")
      (value "47R")
      (footprint "CHIP_R_1206")
      (description "RES SMD 47 OHM 1% 1/4W 1206")
      (fields
        (field (name "MANUFACTURER") "Vishay")
        (field (name "MANUFACTURER PART NUMBER") "CRCW120647R0FKEA")
      )
      (libsource (lib "Pedals SMD") (part "CRCW120647R0FKEA"))
    )
    (comp (ref "R116")
      (value "47k")
      (footprint "CHIP_R_1206")
      (description "RES SMD 47K OHM 1% 1/4W 1206")
      (fields
        (field (name "MANUFACTURER") "Vishay")
        (field (name "MANUFACTURER PART NUMBER") "CRCW120647K0FKEA")
      )
      (libsource (lib "Pedals SMD") (part "CRCW120647K0FKEA"))
    )
    (comp (ref "R117")
      (value "47k")
      (footprint "CHIP_R_1206")
      (description "RES SMD 47K OHM 1% 1/4W 1206")
      (fields
        (field (name "MANUFACTURER") "Vishay")
        (field (name "MANUFACTURER PART NUMBER") "CRCW120647K0FKEA")
      )
      (libsource (lib "Pedals SMD") (part "CRCW120647K0FKEA"))
    )
    (comp (ref "REG1")
      (value "78M33")
      (footprint "SOT223")
      (description "IC REG LIN 3.3V 500MA SOT223-4")
      (fields
        (field (name "MANUFACTURER") "Texas Instruments")
        (field (name "MANUFACTURER PART NUMBER") "UA78M33CDCYR")
      )
      (libsource (lib "Pedals SMD") (part "UA78M33CDCYR"))
    )
    (comp (ref "S1") (value "EC11") (footprint "ALPHA_EC11") (libsource (lib "Pedals") (part "ENC_EC11")))
    (comp (ref "TAPFSW")
      (value "~")
      (footprint "JST-XH-02")
      (description "2 Pins male XH header")
      (libsource (lib "Pedals") (part "JST-XH-02"))
    )
    (comp (ref "TAPLED")
      (value "~")
      (footprint "JST-XH-02")
      (description "2 Pins male XH header")
      (libsource (lib "Pedals") (part "JST-XH-02"))
    )
    (comp (ref "TAP_BRIGHT")
      (value "10kB")
      (footprint "BOURNS_3362P")
      (description "10k Lin 3362P trimmer")
      (libsource (lib "Pedals") (part "TRIM_10kB_3362P"))
    )
    (comp (ref "U1")
      (value "ATMEGA1284")
      (footprint "TQFP44")
      (description "Integrated Circuit")
      (fields (field (name "MANUFACTURER_PART_NUMBER") "ATMEGA1284-AU"))
      (libsource (lib "Pedals SMD") (part "ATMEGA1284-AU"))
    )
    (comp (ref "UART")
      (value "J_HEADER_2PINS_FEM")
      (footprint "HEADER_2Pins_FEM")
      (description "2 Pins female header")
      (libsource (lib "Pedals") (part "J_HEADER_2PINS_FEM"))
    )
    (comp (ref "VOLUME")
      (value "100kB")
      (footprint "ALPHA_9MM_TOP_NOMH")
      (description "100k Lin potentiometer round shaft")
      (libsource (lib "Pedals") (part "POT_100kB_ALPHA_9mm"))
    )
    (comp (ref "Y100")
      (value "ABS07")
      (footprint "ABS-07")
      (description "CRYSTAL 32.7680KHZ 12.5PF SMD")
      (fields
        (field (name "MANUFACTURER") "Abracon")
        (field (name "MANUFACTURER PART NUMBER") "ABS07-32.768KHZ-T")
      )
      (libsource (lib "Pedals SMD") (part "ABS07-32.768KHZ-T"))
    )
  )
  (nets
    (net (code "1") (name "+3.3V") (class "Default")
      (node (ref "C105") (pin "1") (pinfunction "1_1") (pintype "passive"))
      (node (ref "C107") (pin "1") (pinfunction "1_1") (pintype "passive"))
      (node (ref "C11") (pin "1") (pinfunction "1_1") (pintype "passive"))
      (node (ref "C12") (pin "2") (pinfunction "2_2") (pintype "passive"))
      (node (ref "C13") (pin "1") (pinfunction "1_1") (pintype "passive"))
      (node (ref "C14") (pin "1") (pinfunction "1_1") (pintype "passive"))
      (node (ref "C17") (pin "1") (pinfunction "1_1") (pintype "passive"))
      (node (ref "C18") (pin "+") (pinfunction "+_+") (pintype "passive"))
      (node (ref "C3") (pin "1") (pinfunction "1_1") (pintype "passive"))
      (node (ref "C4") (pin "+") (pinfunction "+_+") (pintype "passive"))
      (node (ref "C5") (pin "1") (pinfunction "1_1") (pintype "passive"))
      (node (ref "C6") (pin "1") (pinfunction "1_1") (pintype "passive"))
      (node (ref "C7") (pin "1") (pinfunction "1_1") (pintype "passive"))
      (node (ref "C9") (pin "2") (pinfunction "2_2") (pintype "passive"))
      (node (ref "D0_4") (pin "2") (pinfunction "2_2") (pintype "passive"))
      (node (ref "D0_8") (pin "2") (pinfunction "2_2") (pintype "passive"))
      (node (ref "D1_5") (pin "2") (pinfunction "2_2") (pintype "passive"))
      (node (ref "D1_9") (pin "2") (pinfunction "2_2") (pintype "passive"))
      (node (ref "D2_10") (pin "2") (pinfunction "2_2") (pintype "passive"))
      (node (ref "D2_6") (pin "2") (pinfunction "2_2") (pintype "passive"))
      (node (ref "D3") (pin "1") (pinfunction "1_1") (pintype "passive"))
      (node (ref "D3_11") (pin "2") (pinfunction "2_2") (pintype "passive"))
      (node (ref "D3_7") (pin "2") (pinfunction "2_2") (pintype "passive"))
      (node (ref "D4_12") (pin "2") (pinfunction "2_2") (pintype "passive"))
      (node (ref "D5_13") (pin "2") (pinfunction "2_2") (pintype "passive"))
      (node (ref "D6_14") (pin "2") (pinfunction "2_2") (pintype "passive"))
      (node (ref "D7_15") (pin "2") (pinfunction "2_2") (pintype "passive"))
      (node (ref "EXPR") (pin "R") (pinfunction "R_R") (pintype "passive"))
      (node (ref "IC1") (pin "3") (pinfunction "W_3") (pintype "passive"))
      (node (ref "IC1") (pin "7") (pinfunction "HOLD_7") (pintype "passive"))
      (node (ref "IC1") (pin "8") (pinfunction "VCC_8") (pintype "power_in"))
      (node (ref "IC101") (pin "13") (pinfunction "T0_13") (pintype "passive"))
      (node (ref "IC101") (pin "23") (pinfunction "DVD_23") (pintype "passive"))
      (node (ref "IC101") (pin "6") (pinfunction "AVD_6") (pintype "passive"))
      (node (ref "IC101") (pin "8") (pinfunction "DVD_8") (pintype "passive"))
      (node (ref "IC102") (pin "4") (pinfunction "VCC_4") (pintype "power_in"))
      (node (ref "IC2") (pin "5") (pinfunction "VCC_5") (pintype "passive"))
      (node (ref "IC3") (pin "24") (pinfunction "VDD_24") (pintype "passive"))
      (node (ref "IC5") (pin "16") (pinfunction "VDD_16") (pintype "passive"))
      (node (ref "IC6") (pin "1") (pinfunction "~{RESET}_1") (pintype "passive"))
      (node (ref "IC6") (pin "8") (pinfunction "VLOGIC_8") (pintype "passive"))
      (node (ref "K1") (pin "1") (pinfunction "+_1") (pintype "passive"))
      (node (ref "L1") (pin "2") (pinfunction "2_2") (pintype "passive"))
      (node (ref "OK1") (pin "6") (pinfunction "VCC_6") (pintype "passive"))
      (node (ref "POT0") (pin "3") (pinfunction "3_3") (pintype "passive"))
      (node (ref "POT1") (pin "3") (pinfunction "3_3") (pintype "passive"))
      (node (ref "POT2") (pin "3") (pinfunction "3_3") (pintype "passive"))
      (node (ref "POT3") (pin "3") (pinfunction "3_3") (pintype "passive"))
      (node (ref "PROG") (pin "5") (pinfunction "5_5") (pintype "passive"))
      (node (ref "PROG2") (pin "2") (pinfunction "2_2") (pintype "passive"))
      (node (ref "R104") (pin "2") (pinfunction "2_2") (pintype "passive"))
      (node (ref "R4") (pin "2") (pinfunction "2_2") (pintype "passive"))
      (node (ref "R5") (pin "2") (pinfunction "2_2") (pintype "passive"))
      (node (ref "R7") (pin "1") (pinfunction "1_1") (pintype "passive"))
      (node (ref "R9") (pin "2") (pinfunction "2_2") (pintype "passive"))
      (node (ref "REG1") (pin "3") (pinfunction "OUTPUT_3") (pintype "power_in"))
      (node (ref "U1") (pin "17") (pinfunction "VCC_2_17") (pintype "passive"))
      (node (ref "U1") (pin "38") (pinfunction "VCC_3_38") (pintype "passive"))
      (node (ref "U1") (pin "5") (pinfunction "VCC_1_5") (pintype "passive"))
    )
    (net (code "2") (name "+9V") (class "Default")
      (node (ref "C1") (pin "+") (pinfunction "+_+") (pintype "passive"))
      (node (ref "C15") (pin "1") (pinfunction "1_1") (pintype "passive"))
      (node (ref "C16") (pin "+") (pinfunction "+_+") (pintype "passive"))
      (node (ref "C2") (pin "1") (pinfunction "1_1") (pintype "passive"))
      (node (ref "D1") (pin "1") (pinfunction "1_1") (pintype "passive"))
      (node (ref "DC") (pin "1") (pinfunction "S_1") (pintype "passive"))
      (node (ref "IC6") (pin "6") (pinfunction "VDD_6") (pintype "passive"))
      (node (ref "R115") (pin "1") (pinfunction "1_1") (pintype "passive"))
      (node (ref "REG1") (pin "1") (pinfunction "INPUT_1") (pintype "power_in"))
    )
    (net (code "3") (name "/A") (class "Default")
      (node (ref "IC6") (pin "3") (pinfunction "A_3") (pintype "passive"))
      (node (ref "R109") (pin "2") (pinfunction "2_2") (pintype "passive"))
      (node (ref "R110") (pin "1") (pinfunction "1_1") (pintype "passive"))
    )
    (net (code "4") (name "/AREF") (class "Default")
      (node (ref "U1") (pin "29") (pinfunction "AREF_29") (pintype "passive"))
    )
    (net (code "5") (name "/AVCC") (class "Default")
      (node (ref "C8") (pin "1") (pinfunction "1_1") (pintype "passive"))
      (node (ref "L1") (pin "1") (pinfunction "1_1") (pintype "passive"))
      (node (ref "U1") (pin "27") (pinfunction "AVCC_27") (pintype "passive"))
    )
    (net (code "6") (name "/B") (class "Default")
      (node (ref "IC6") (pin "5") (pinfunction "B_5") (pintype "passive"))
      (node (ref "R107") (pin "2") (pinfunction "2_2") (pintype "passive"))
      (node (ref "R108") (pin "1") (pinfunction "1_1") (pintype "passive"))
    )
    (net (code "7") (name "/BYP_FSW0") (class "Default")
      (node (ref "FSW") (pin "1") (pinfunction "S_1") (pintype "passive"))
      (node (ref "U1") (pin "12") (pinfunction "(PCINT27/TXD1/INT1)_PD3_12") (pintype "passive"))
    )
    (net (code "8") (name "/BYP_K0") (class "Default")
      (node (ref "R12") (pin "1") (pinfunction "1_1") (pintype "passive"))
      (node (ref "U1") (pin "42") (pinfunction "PB2_(AIN0/INT2/PCINT10)_42") (pintype "passive"))
    )
    (net (code "9") (name "/BYP_LED0") (class "Default")
      (node (ref "R10") (pin "1") (pinfunction "1_1") (pintype "passive"))
      (node (ref "U1") (pin "11") (pinfunction "(PCINT26/RXD1/INT0)_PD2_11") (pintype "passive"))
    )
    (net (code "10") (name "/BYP_OK0") (class "Default")
      (node (ref "R11") (pin "1") (pinfunction "1_1") (pintype "passive"))
      (node (ref "U1") (pin "41") (pinfunction "PB1_(T1/CLKO/PCINT9)_41") (pintype "passive"))
    )
    (net (code "11") (name "/DPOT_LE0") (class "Default")
      (node (ref "IC6") (pin "12") (pinfunction "~{SYNC}_12") (pintype "passive"))
      (node (ref "U1") (pin "43") (pinfunction "PB3_(AIN1/OC0A/PCINT11)_43") (pintype "passive"))
    )
    (net (code "12") (name "/EEPR_LE0") (class "Default")
      (node (ref "IC1") (pin "1") (pinfunction "S_1") (pintype "passive"))
      (node (ref "R5") (pin "1") (pinfunction "1_1") (pintype "passive"))
      (node (ref "U1") (pin "25") (pinfunction "PC6_(TOSC1/PCINT22)_25") (pintype "passive"))
    )
    (net (code "13") (name "/EXPR0_P") (class "Default")
      (node (ref "EXPR") (pin "SN") (pinfunction "SN_SN") (pintype "passive"))
      (node (ref "U1") (pin "26") (pinfunction "PC7_(TOSC2/PCINT23)_26") (pintype "passive"))
    )
    (net (code "14") (name "/EXPR0_W") (class "Default")
      (node (ref "EXPR") (pin "T") (pinfunction "T_T") (pintype "passive"))
      (node (ref "U1") (pin "35") (pinfunction "PA2_(ADC2/PCINT2)_35") (pintype "passive"))
    )
    (net (code "15") (name "/FV1_P0") (class "Default")
      (node (ref "IC101") (pin "20") (pinfunction "POT0_20") (pintype "passive"))
      (node (ref "U1") (pin "15") (pinfunction "(PCINT30/OC2B/ICP1)_PD6_15") (pintype "passive"))
    )
    (net (code "16") (name "/FV1_P1") (class "Default")
      (node (ref "IC101") (pin "21") (pinfunction "POT1_21") (pintype "passive"))
      (node (ref "U1") (pin "14") (pinfunction "(PCINT29/OC1A)_PD5_14") (pintype "passive"))
    )
    (net (code "17") (name "/FV1_P2") (class "Default")
      (node (ref "IC101") (pin "22") (pinfunction "POT2_22") (pintype "passive"))
      (node (ref "U1") (pin "13") (pinfunction "(PCINT28/XCK1/OC1B)_PD4_13") (pintype "passive"))
    )
    (net (code "18") (name "/FV1_S0") (class "Default")
      (node (ref "IC101") (pin "16") (pinfunction "S0_16") (pintype "passive"))
      (node (ref "U1") (pin "19") (pinfunction "(PCINT16/SCL)_PC0_19") (pintype "passive"))
    )
    (net (code "19") (name "/FV1_S1") (class "Default")
      (node (ref "IC101") (pin "17") (pinfunction "S1_17") (pintype "passive"))
      (node (ref "U1") (pin "20") (pinfunction "(PCINT17/SDA)_PC1_20") (pintype "passive"))
    )
    (net (code "20") (name "/FV1_S2") (class "Default")
      (node (ref "IC101") (pin "18") (pinfunction "S2_18") (pintype "passive"))
      (node (ref "U1") (pin "21") (pinfunction "(PCINT18/TCK)_PC2_21") (pintype "passive"))
    )
    (net (code "21") (name "/INPUT") (class "Default")
      (node (ref "INPUT") (pin "T") (pinfunction "T_T") (pintype "passive"))
      (node (ref "K1") (pin "6") (pinfunction "P_6") (pintype "passive"))
    )
    (net (code "22") (name "/MISO") (class "Default")
      (node (ref "IC1") (pin "2") (pinfunction "Q_2") (pintype "passive"))
      (node (ref "PROG") (pin "2") (pinfunction "2_2") (pintype "passive"))
      (node (ref "U1") (pin "2") (pinfunction "(PCINT14/OC3A/MISO)_PB6_2") (pintype "passive"))
    )
    (net (code "23") (name "/MOSI") (class "Default")
      (node (ref "IC1") (pin "5") (pinfunction "D_5") (pintype "passive"))
      (node (ref "IC3") (pin "2") (pinfunction "SDI_2") (pintype "passive"))
      (node (ref "IC5") (pin "2") (pinfunction "SDI_2") (pintype "passive"))
      (node (ref "IC6") (pin "10") (pinfunction "DIN_10") (pintype "passive"))
      (node (ref "PROG") (pin "3") (pinfunction "3_3") (pintype "passive"))
      (node (ref "U1") (pin "1") (pinfunction "(PCINT13/MOSI)_PB5_1") (pintype "passive"))
    )
    (net (code "24") (name "/OUTPUT") (class "Default")
      (node (ref "K1") (pin "3") (pinfunction "P_3") (pintype "passive"))
      (node (ref "OK2") (pin "6") (pinfunction "COL_6") (pintype "passive"))
      (node (ref "OUTPUT") (pin "T") (pinfunction "T_T") (pintype "passive"))
    )
    (net (code "25") (name "/P0_W") (class "Default")
      (node (ref "POT0") (pin "2") (pinfunction "2_2") (pintype "passive"))
      (node (ref "U1") (pin "34") (pinfunction "PA3_(ADC3/PCINT3)_34") (pintype "passive"))
    )
    (net (code "26") (name "/P1_W") (class "Default")
      (node (ref "POT1") (pin "2") (pinfunction "2_2") (pintype "passive"))
      (node (ref "U1") (pin "36") (pinfunction "PA1_(ADC1/PCINT1)_36") (pintype "passive"))
    )
    (net (code "27") (name "/P2_W") (class "Default")
      (node (ref "POT2") (pin "2") (pinfunction "2_2") (pintype "passive"))
      (node (ref "U1") (pin "33") (pinfunction "PA4_(ADC4/PCINT4)_33") (pintype "passive"))
    )
    (net (code "28") (name "/P3_W") (class "Default")
      (node (ref "POT3") (pin "2") (pinfunction "2_2") (pintype "passive"))
      (node (ref "U1") (pin "37") (pinfunction "PA0_(ADC0/PCINT0)_37") (pintype "passive"))
    )
    (net (code "29") (name "/PS_0") (class "Default")
      (node (ref "D0_8") (pin "1") (pinfunction "1_1") (pintype "passive"))
      (node (ref "IC3") (pin "12") (pinfunction "OUT7_12") (pintype "passive"))
    )
    (net (code "30") (name "/PS_1") (class "Default")
      (node (ref "D1_9") (pin "1") (pinfunction "1_1") (pintype "passive"))
      (node (ref "IC3") (pin "11") (pinfunction "OUT6_11") (pintype "passive"))
    )
    (net (code "31") (name "/PS_2") (class "Default")
      (node (ref "D2_10") (pin "1") (pinfunction "1_1") (pintype "passive"))
      (node (ref "IC3") (pin "10") (pinfunction "OUT5_10") (pintype "passive"))
    )
    (net (code "32") (name "/PS_3") (class "Default")
      (node (ref "D3_11") (pin "1") (pinfunction "1_1") (pintype "passive"))
      (node (ref "IC3") (pin "9") (pinfunction "OUT4_9") (pintype "passive"))
    )
    (net (code "33") (name "/PS_4") (class "Default")
      (node (ref "D4_12") (pin "1") (pinfunction "1_1") (pintype "passive"))
      (node (ref "IC3") (pin "8") (pinfunction "OUT3_8") (pintype "passive"))
    )
    (net (code "34") (name "/PS_5") (class "Default")
      (node (ref "D5_13") (pin "1") (pinfunction "1_1") (pintype "passive"))
      (node (ref "IC3") (pin "7") (pinfunction "OUT2_7") (pintype "passive"))
    )
    (net (code "35") (name "/PS_6") (class "Default")
      (node (ref "D6_14") (pin "1") (pinfunction "1_1") (pintype "passive"))
      (node (ref "IC3") (pin "6") (pinfunction "OUT1_6") (pintype "passive"))
    )
    (net (code "36") (name "/PS_7") (class "Default")
      (node (ref "D7_15") (pin "1") (pinfunction "1_1") (pintype "passive"))
      (node (ref "IC3") (pin "5") (pinfunction "OUT0_5") (pintype "passive"))
    )
    (net (code "37") (name "/PS_8") (class "Default")
      (node (ref "D7_15") (pin "3") (pinfunction "3_3") (pintype "passive"))
      (node (ref "IC3") (pin "20") (pinfunction "OUT15_20") (pintype "passive"))
    )
    (net (code "38") (name "/PS_9") (class "Default")
      (node (ref "D6_14") (pin "3") (pinfunction "3_3") (pintype "passive"))
      (node (ref "IC3") (pin "19") (pinfunction "OUT14_19") (pintype "passive"))
    )
    (net (code "39") (name "/PS_10") (class "Default")
      (node (ref "D5_13") (pin "3") (pinfunction "3_3") (pintype "passive"))
      (node (ref "IC3") (pin "18") (pinfunction "OUT13_18") (pintype "passive"))
    )
    (net (code "40") (name "/PS_11") (class "Default")
      (node (ref "D4_12") (pin "3") (pinfunction "3_3") (pintype "passive"))
      (node (ref "IC3") (pin "17") (pinfunction "OUT12_17") (pintype "passive"))
    )
    (net (code "41") (name "/PS_12") (class "Default")
      (node (ref "D3_11") (pin "3") (pinfunction "3_3") (pintype "passive"))
      (node (ref "IC3") (pin "16") (pinfunction "OUT11_16") (pintype "passive"))
    )
    (net (code "42") (name "/PS_13") (class "Default")
      (node (ref "D2_10") (pin "3") (pinfunction "3_3") (pintype "passive"))
      (node (ref "IC3") (pin "15") (pinfunction "OUT10_15") (pintype "passive"))
    )
    (net (code "43") (name "/PS_14") (class "Default")
      (node (ref "D1_9") (pin "3") (pinfunction "3_3") (pintype "passive"))
      (node (ref "IC3") (pin "14") (pinfunction "OUT9_14") (pintype "passive"))
    )
    (net (code "44") (name "/PS_15") (class "Default")
      (node (ref "D0_8") (pin "3") (pinfunction "3_3") (pintype "passive"))
      (node (ref "IC3") (pin "13") (pinfunction "OUT8_13") (pintype "passive"))
    )
    (net (code "45") (name "/PS_ENC_A") (class "Default")
      (node (ref "S1") (pin "1") (pinfunction "A_1") (pintype "passive"))
      (node (ref "U1") (pin "32") (pinfunction "PA5_(ADC5/PCINT5)_32") (pintype "passive"))
    )
    (net (code "46") (name "/PS_ENC_B") (class "Default")
      (node (ref "S1") (pin "3") (pinfunction "B_3") (pintype "passive"))
      (node (ref "U1") (pin "31") (pinfunction "PA6_(ADC6/PCINT6)_31") (pintype "passive"))
    )
    (net (code "47") (name "/PS_ENC_SW") (class "Default")
      (node (ref "S1") (pin "4") (pinfunction "4_4") (pintype "passive"))
      (node (ref "U1") (pin "30") (pinfunction "PA7_(ADC7/PCINT7)_30") (pintype "passive"))
    )
    (net (code "48") (name "/PS_LE0") (class "Default")
      (node (ref "IC3") (pin "4") (pinfunction "LE_4") (pintype "passive"))
      (node (ref "U1") (pin "23") (pinfunction "PC4_(TDO/PCINT20)_23") (pintype "passive"))
    )
    (net (code "49") (name "/RESET") (class "Default")
      (node (ref "PROG") (pin "4") (pinfunction "4_4") (pintype "passive"))
      (node (ref "R4") (pin "1") (pinfunction "1_1") (pintype "passive"))
      (node (ref "U1") (pin "4") (pinfunction "RESET_4") (pintype "passive"))
    )
    (net (code "50") (name "/RETURN") (class "Default")
      (node (ref "C114") (pin "-") (pinfunction "-_-") (pintype "passive"))
      (node (ref "K1") (pin "4") (pinfunction "S_4") (pintype "passive"))
      (node (ref "R114") (pin "2") (pinfunction "2_2") (pintype "passive"))
    )
    (net (code "51") (name "/RX0") (class "Default")
      (node (ref "IC2") (pin "2") (pinfunction "A_2") (pintype "passive"))
      (node (ref "OK1") (pin "5") (pinfunction "VO_5") (pintype "passive"))
      (node (ref "R7") (pin "2") (pinfunction "2_2") (pintype "passive"))
      (node (ref "U1") (pin "9") (pinfunction "(PCINT24/RXD0/T3)_PD0_9") (pintype "passive"))
    )
    (net (code "52") (name "/SCK") (class "Default")
      (node (ref "IC1") (pin "6") (pinfunction "C_6") (pintype "passive"))
      (node (ref "IC3") (pin "3") (pinfunction "CLK_3") (pintype "passive"))
      (node (ref "IC5") (pin "3") (pinfunction "CLK_3") (pintype "passive"))
      (node (ref "IC6") (pin "11") (pinfunction "SCLK_11") (pintype "passive"))
      (node (ref "PROG") (pin "1") (pinfunction "1_1") (pintype "passive"))
      (node (ref "U1") (pin "3") (pinfunction "(PCINT15/OC3B/SCK)_PB7_3") (pintype "passive"))
    )
    (net (code "53") (name "/SCL") (class "Default")
      (node (ref "IC101") (pin "14") (pinfunction "SCK_14") (pintype "passive"))
      (node (ref "IC102") (pin "1") (pinfunction "SCL_1") (pintype "passive"))
      (node (ref "PROG2") (pin "3") (pinfunction "3_3") (pintype "passive"))
    )
    (net (code "54") (name "/SDA") (class "Default")
      (node (ref "IC101") (pin "15") (pinfunction "SDA_15") (pintype "passive"))
      (node (ref "IC102") (pin "3") (pinfunction "SDA_3") (pintype "passive"))
      (node (ref "PROG2") (pin "4") (pinfunction "4_4") (pintype "passive"))
    )
    (net (code "55") (name "/SEND") (class "Default")
      (node (ref "C100") (pin "2") (pinfunction "2_2") (pintype "passive"))
      (node (ref "K1") (pin "5") (pinfunction "S_5") (pintype "passive"))
      (node (ref "R100") (pin "2") (pinfunction "2_2") (pintype "passive"))
    )
    (net (code "56") (name "/TAP_0") (class "Default")
      (node (ref "D0_4") (pin "1") (pinfunction "1_1") (pintype "passive"))
      (node (ref "IC5") (pin "5") (pinfunction "OUT0_5") (pintype "passive"))
    )
    (net (code "57") (name "/TAP_1") (class "Default")
      (node (ref "D1_5") (pin "1") (pinfunction "1_1") (pintype "passive"))
      (node (ref "IC5") (pin "6") (pinfunction "OUT1_6") (pintype "passive"))
    )
    (net (code "58") (name "/TAP_2") (class "Default")
      (node (ref "D2_6") (pin "1") (pinfunction "1_1") (pintype "passive"))
      (node (ref "IC5") (pin "7") (pinfunction "OUT2_7") (pintype "passive"))
    )
    (net (code "59") (name "/TAP_3") (class "Default")
      (node (ref "D3_7") (pin "1") (pinfunction "1_1") (pintype "passive"))
      (node (ref "IC5") (pin "8") (pinfunction "OUT3_8") (pintype "passive"))
    )
    (net (code "60") (name "/TAP_4") (class "Default")
      (node (ref "D0_4") (pin "3") (pinfunction "3_3") (pintype "passive"))
      (node (ref "IC5") (pin "9") (pinfunction "OUT4_9") (pintype "passive"))
    )
    (net (code "61") (name "/TAP_5") (class "Default")
      (node (ref "D1_5") (pin "3") (pinfunction "3_3") (pintype "passive"))
      (node (ref "IC5") (pin "10") (pinfunction "OUT5_10") (pintype "passive"))
    )
    (net (code "62") (name "/TAP_6") (class "Default")
      (node (ref "D2_6") (pin "3") (pinfunction "3_3") (pintype "passive"))
      (node (ref "IC5") (pin "11") (pinfunction "OUT6_11") (pintype "passive"))
    )
    (net (code "63") (name "/TAP_7") (class "Default")
      (node (ref "D3_7") (pin "3") (pinfunction "3_3") (pintype "passive"))
      (node (ref "IC5") (pin "12") (pinfunction "OUT7_12") (pintype "passive"))
    )
    (net (code "64") (name "/TAP_FSW0") (class "Default")
      (node (ref "TAPFSW") (pin "2") (pinfunction "S_2") (pintype "passive"))
      (node (ref "U1") (pin "22") (pinfunction "(PCINT19/TMS)_PC3_22") (pintype "passive"))
    )
    (net (code "65") (name "/TAP_LE0") (class "Default")
      (node (ref "IC5") (pin "4") (pinfunction "LE_4") (pintype "passive"))
      (node (ref "U1") (pin "24") (pinfunction "PC5_(TDI/PCINT21)_24") (pintype "passive"))
    )
    (net (code "66") (name "/TAP_LED0") (class "Default")
      (node (ref "R15") (pin "1") (pinfunction "1_1") (pintype "passive"))
      (node (ref "U1") (pin "16") (pinfunction "(PCINT31/OC2A)_PD7_16") (pintype "passive"))
    )
    (net (code "67") (name "/TX0") (class "Default")
      (node (ref "U1") (pin "10") (pinfunction "(PCINT25/TXD0)_PD1_10") (pintype "passive"))
      (node (ref "UART") (pin "1") (pinfunction "1_1") (pintype "passive"))
    )
    (net (code "68") (name "/XTAL1") (class "Default")
      (node (ref "U1") (pin "8") (pinfunction "XTAL1_8") (pintype "passive"))
    )
    (net (code "69") (name "/XTAL2") (class "Default")
      (node (ref "U1") (pin "7") (pinfunction "XTAL2_7") (pintype "passive"))
    )
    (net (code "70") (name "GND") (class "Default")
      (node (ref "BYPLED") (pin "2") (pinfunction "S_2") (pintype "passive"))
      (node (ref "C1") (pin "-") (pinfunction "-_-") (pintype "passive"))
      (node (ref "C10") (pin "2") (pinfunction "2_2") (pintype "passive"))
      (node (ref "C102") (pin "2") (pinfunction "2_2") (pintype "passive"))
      (node (ref "C103") (pin "-") (pinfunction "-_-") (pintype "passive"))
      (node (ref "C104") (pin "2") (pinfunction "2_2") (pintype "passive"))
      (node (ref "C105") (pin "2") (pinfunction "2_2") (pintype "passive"))
      (node (ref "C106") (pin "-") (pinfunction "-_-") (pintype "passive"))
      (node (ref "C107") (pin "2") (pinfunction "2_2") (pintype "passive"))
      (node (ref "C109") (pin "2") (pinfunction "2_2") (pintype "passive"))
      (node (ref "C11") (pin "2") (pinfunction "2_2") (pintype "passive"))
      (node (ref "C115") (pin "-") (pinfunction "-_-") (pintype "passive"))
      (node (ref "C116") (pin "-") (pinfunction "-_-") (pintype "passive"))
      (node (ref "C117") (pin "2") (pinfunction "2_2") (pintype "passive"))
      (node (ref "C12") (pin "1") (pinfunction "1_1") (pintype "passive"))
      (node (ref "C13") (pin "2") (pinfunction "2_2") (pintype "passive"))
      (node (ref "C14") (pin "2") (pinfunction "2_2") (pintype "passive"))
      (node (ref "C15") (pin "2") (pinfunction "2_2") (pintype "passive"))
      (node (ref "C16") (pin "-") (pinfunction "-_-") (pintype "passive"))
      (node (ref "C17") (pin "2") (pinfunction "2_2") (pintype "passive"))
      (node (ref "C18") (pin "-") (pinfunction "-_-") (pintype "passive"))
      (node (ref "C19") (pin "-") (pinfunction "-_-") (pintype "passive"))
      (node (ref "C2") (pin "2") (pinfunction "2_2") (pintype "passive"))
      (node (ref "C3") (pin "2") (pinfunction "2_2") (pintype "passive"))
      (node (ref "C4") (pin "-") (pinfunction "-_-") (pintype "passive"))
      (node (ref "C5") (pin "2") (pinfunction "2_2") (pintype "passive"))
      (node (ref "C6") (pin "2") (pinfunction "2_2") (pintype "passive"))
      (node (ref "C7") (pin "2") (pinfunction "2_2") (pintype "passive"))
      (node (ref "C8") (pin "2") (pinfunction "2_2") (pintype "passive"))
      (node (ref "C9") (pin "1") (pinfunction "1_1") (pintype "passive"))
      (node (ref "D1") (pin "2") (pinfunction "2_2") (pintype "passive"))
      (node (ref "DC") (pin "2") (pinfunction "S_2") (pintype "passive"))
      (node (ref "EXPR") (pin "S") (pinfunction "S_S") (pintype "passive"))
      (node (ref "FSW") (pin "2") (pinfunction "S_2") (pintype "passive"))
      (node (ref "IC1") (pin "4") (pinfunction "VSS_4") (pintype "power_in"))
      (node (ref "IC100") (pin "11") (pinfunction "V-_11") (pintype "power_in"))
      (node (ref "IC101") (pin "11") (pinfunction "GND_11") (pintype "passive"))
      (node (ref "IC101") (pin "12") (pinfunction "T1_12") (pintype "passive"))
      (node (ref "IC101") (pin "19") (pinfunction "GND_19") (pintype "passive"))
      (node (ref "IC101") (pin "24") (pinfunction "GND_24") (pintype "passive"))
      (node (ref "IC101") (pin "25") (pinfunction "REFN_25") (pintype "passive"))
      (node (ref "IC101") (pin "4") (pinfunction "GND_4") (pintype "passive"))
      (node (ref "IC101") (pin "7") (pinfunction "GND_7") (pintype "passive"))
      (node (ref "IC102") (pin "2") (pinfunction "VSS_2") (pintype "power_in"))
      (node (ref "IC102") (pin "5") (pinfunction "WP_5") (pintype "passive"))
      (node (ref "IC2") (pin "3") (pinfunction "GND_3") (pintype "passive"))
      (node (ref "IC3") (pin "1") (pinfunction "GND_1") (pintype "passive"))
      (node (ref "IC3") (pin "21") (pinfunction "~{OE}_21") (pintype "passive"))
      (node (ref "IC5") (pin "1") (pinfunction "GND_1") (pintype "passive"))
      (node (ref "IC5") (pin "13") (pinfunction "~{OE}_13") (pintype "passive"))
      (node (ref "IC6") (pin "2") (pinfunction "VSS_2") (pintype "passive"))
      (node (ref "IC6") (pin "9") (pinfunction "GND_9") (pintype "passive"))
      (node (ref "INPUT") (pin "S") (pinfunction "S_S") (pintype "passive"))
      (node (ref "MIDI_THRU") (pin "S") (pinfunction "S_S") (pintype "passive"))
      (node (ref "OK1") (pin "4") (pinfunction "GND_4") (pintype "passive"))
      (node (ref "OK2") (pin "3") (pinfunction "C_3") (pintype "passive"))
      (node (ref "OK2") (pin "4") (pinfunction "EMIT_4") (pintype "passive"))
      (node (ref "OUTPUT") (pin "S") (pinfunction "S_S") (pintype "passive"))
      (node (ref "POT0") (pin "1") (pinfunction "1_1") (pintype "passive"))
      (node (ref "POT1") (pin "1") (pinfunction "1_1") (pintype "passive"))
      (node (ref "POT2") (pin "1") (pinfunction "1_1") (pintype "passive"))
      (node (ref "POT3") (pin "1") (pinfunction "1_1") (pintype "passive"))
      (node (ref "PROG") (pin "6") (pinfunction "6_6") (pintype "passive"))
      (node (ref "PROG2") (pin "1") (pinfunction "1_1") (pintype "passive"))
      (node (ref "Q1") (pin "2") (pinfunction "E_2") (pintype "passive"))
      (node (ref "R100") (pin "1") (pinfunction "1_1") (pintype "passive"))
      (node (ref "R114") (pin "1") (pinfunction "1_1") (pintype "passive"))
      (node (ref "R117") (pin "1") (pinfunction "1_1") (pintype "passive"))
      (node (ref "R13") (pin "1") (pinfunction "1_1") (pintype "passive"))
      (node (ref "R14") (pin "1") (pinfunction "1_1") (pintype "passive"))
      (node (ref "REG1") (pin "2") (pinfunction "COMMON_2") (pintype "power_in"))
      (node (ref "S1") (pin "2") (pinfunction "C_2") (pintype "passive"))
      (node (ref "S1") (pin "5") (pinfunction "5_5") (pintype "passive"))
      (node (ref "TAPFSW") (pin "1") (pinfunction "S_1") (pintype "passive"))
      (node (ref "TAPLED") (pin "2") (pinfunction "S_2") (pintype "passive"))
      (node (ref "U1") (pin "18") (pinfunction "GND_2_18") (pintype "passive"))
      (node (ref "U1") (pin "28") (pinfunction "GND_3_28") (pintype "passive"))
      (node (ref "U1") (pin "39") (pinfunction "GND_4_39") (pintype "passive"))
      (node (ref "U1") (pin "6") (pinfunction "GND_1_6") (pintype "passive"))
    )
    (net (code "71") (name "Net-(BYPLEDB-S)") (class "Default")
      (node (ref "BYPLED") (pin "1") (pinfunction "S_1") (pintype "passive"))
      (node (ref "BYP_BRIGHT") (pin "2") (pinfunction "2_2") (pintype "passive"))
      (node (ref "BYP_BRIGHT") (pin "3") (pinfunction "3_3") (pintype "passive"))
    )
    (net (code "72") (name "Net-(BYP_BRIGHT-Pad1)") (class "Default")
      (node (ref "BYP_BRIGHT") (pin "1") (pinfunction "1_1") (pintype "passive"))
      (node (ref "R10") (pin "2") (pinfunction "2_2") (pintype "passive"))
    )
    (net (code "73") (name "Net-(C10-Pad1)") (class "Default")
      (node (ref "C10") (pin "1") (pinfunction "1_1") (pintype "passive"))
      (node (ref "MIDI_IN") (pin "S") (pinfunction "S_S") (pintype "passive"))
    )
    (net (code "74") (name "Net-(C100-Pad1)") (class "Default")
      (node (ref "C100") (pin "1") (pinfunction "1_1") (pintype "passive"))
      (node (ref "R101") (pin "1") (pinfunction "1_1") (pintype "passive"))
    )
    (net (code "75") (name "Net-(C101-Pad-)") (class "Default")
      (node (ref "C101") (pin "-") (pinfunction "-_-") (pintype "passive"))
      (node (ref "R103") (pin "1") (pinfunction "1_1") (pintype "passive"))
    )
    (net (code "76") (name "Net-(C108-Pad-)") (class "Default")
      (node (ref "C108") (pin "-") (pinfunction "-_-") (pintype "passive"))
      (node (ref "R105") (pin "1") (pinfunction "1_1") (pintype "passive"))
    )
    (net (code "77") (name "Net-(C110-Pad-)") (class "Default")
      (node (ref "C110") (pin "-") (pinfunction "-_-") (pintype "passive"))
      (node (ref "R107") (pin "1") (pinfunction "1_1") (pintype "passive"))
    )
    (net (code "78") (name "Net-(C111-Pad-)") (class "Default")
      (node (ref "C111") (pin "-") (pinfunction "-_-") (pintype "passive"))
      (node (ref "R109") (pin "1") (pinfunction "1_1") (pintype "passive"))
    )
    (net (code "79") (name "Net-(C114-Pad+)") (class "Default")
      (node (ref "C114") (pin "+") (pinfunction "+_+") (pintype "passive"))
      (node (ref "R113") (pin "2") (pinfunction "2_2") (pintype "passive"))
    )
    (net (code "80") (name "Net-(DIV_BRIGHT-Pad1)") (class "Default")
      (node (ref "DIV_BRIGHT") (pin "1") (pinfunction "1_1") (pintype "passive"))
      (node (ref "R14") (pin "2") (pinfunction "2_2") (pintype "passive"))
    )
    (net (code "81") (name "Net-(IC2-Y)") (class "Default")
      (node (ref "IC2") (pin "4") (pinfunction "Y_4") (pintype "passive"))
      (node (ref "R8") (pin "1") (pinfunction "1_1") (pintype "passive"))
    )
    (net (code "82") (name "Net-(IC3-R-EXT)") (class "Default")
      (node (ref "IC3") (pin "23") (pinfunction "R-EXT_23") (pintype "passive"))
      (node (ref "PS_BRIGHT") (pin "2") (pinfunction "2_2") (pintype "passive"))
      (node (ref "PS_BRIGHT") (pin "3") (pinfunction "3_3") (pintype "passive"))
    )
    (net (code "83") (name "Net-(IC5-R-EXT)") (class "Default")
      (node (ref "DIV_BRIGHT") (pin "2") (pinfunction "2_2") (pintype "passive"))
      (node (ref "DIV_BRIGHT") (pin "3") (pinfunction "3_3") (pintype "passive"))
      (node (ref "IC5") (pin "15") (pinfunction "R-EXT_15") (pintype "passive"))
    )
    (net (code "84") (name "Net-(IC6-EXT_CAP)") (class "Default")
      (node (ref "C19") (pin "+") (pinfunction "+_+") (pintype "passive"))
      (node (ref "IC6") (pin "7") (pinfunction "EXT_CAP_7") (pintype "passive"))
    )
    (net (code "85") (name "Net-(IC100A-+IN)") (class "Default")
      (node (ref "C109") (pin "1") (pinfunction "1_1") (pintype "passive"))
      (node (ref "IC100") (pin "3") (pinfunction "+IN_3") (pintype "passive"))
      (node (ref "R105") (pin "2") (pinfunction "2_2") (pintype "passive"))
      (node (ref "R106") (pin "1") (pinfunction "1_1") (pintype "passive"))
    )
    (net (code "86") (name "Net-(IC100A--IN)") (class "Default")
      (node (ref "C111") (pin "+") (pinfunction "+_+") (pintype "passive"))
      (node (ref "IC100") (pin "1") (pinfunction "OUT_1") (pintype "output"))
      (node (ref "IC100") (pin "2") (pinfunction "-IN_2") (pintype "passive"))
    )
    (net (code "87") (name "Net-(IC100B--IN)") (class "Default")
      (node (ref "C112") (pin "2") (pinfunction "2_2") (pintype "passive"))
      (node (ref "IC100") (pin "6") (pinfunction "-IN_6") (pintype "passive"))
      (node (ref "R108") (pin "2") (pinfunction "2_2") (pintype "passive"))
      (node (ref "R110") (pin "2") (pinfunction "2_2") (pintype "passive"))
      (node (ref "VOLUME") (pin "1") (pinfunction "1_1") (pintype "passive"))
    )
    (net (code "88") (name "Net-(IC100B-OUT)") (class "Default")
      (node (ref "C112") (pin "1") (pinfunction "1_1") (pintype "passive"))
      (node (ref "IC100") (pin "7") (pinfunction "OUT_7") (pintype "output"))
      (node (ref "R111") (pin "1") (pinfunction "1_1") (pintype "passive"))
      (node (ref "VOLUME") (pin "2") (pinfunction "2_2") (pintype "passive"))
      (node (ref "VOLUME") (pin "3") (pinfunction "3_3") (pintype "passive"))
    )
    (net (code "89") (name "Net-(IC100C--IN)") (class "Default")
      (node (ref "C113") (pin "2") (pinfunction "2_2") (pintype "passive"))
      (node (ref "IC100") (pin "9") (pinfunction "-IN_9") (pintype "passive"))
      (node (ref "R111") (pin "2") (pinfunction "2_2") (pintype "passive"))
      (node (ref "R112") (pin "1") (pinfunction "1_1") (pintype "passive"))
    )
    (net (code "90") (name "Net-(IC100C-OUT)") (class "Default")
      (node (ref "C113") (pin "1") (pinfunction "1_1") (pintype "passive"))
      (node (ref "IC100") (pin "8") (pinfunction "OUT_8") (pintype "output"))
      (node (ref "R112") (pin "2") (pinfunction "2_2") (pintype "passive"))
      (node (ref "R113") (pin "1") (pinfunction "1_1") (pintype "passive"))
    )
    (net (code "91") (name "Net-(IC100D-+IN)") (class "Default")
      (node (ref "IC100") (pin "12") (pinfunction "+IN_12") (pintype "passive"))
      (node (ref "R101") (pin "2") (pinfunction "2_2") (pintype "passive"))
      (node (ref "R102") (pin "1") (pinfunction "1_1") (pintype "passive"))
    )
    (net (code "92") (name "Net-(IC100D--IN)") (class "Default")
      (node (ref "C101") (pin "+") (pinfunction "+_+") (pintype "passive"))
      (node (ref "C110") (pin "+") (pinfunction "+_+") (pintype "passive"))
      (node (ref "IC100") (pin "13") (pinfunction "-IN_13") (pintype "passive"))
      (node (ref "IC100") (pin "14") (pinfunction "OUT_14") (pintype "output"))
    )
    (net (code "93") (name "Net-(IC101-LIN)") (class "Default")
      (node (ref "C102") (pin "1") (pinfunction "1_1") (pintype "passive"))
      (node (ref "IC101") (pin "1") (pinfunction "LIN_1") (pintype "passive"))
      (node (ref "IC101") (pin "2") (pinfunction "RIN_2") (pintype "passive"))
      (node (ref "R103") (pin "2") (pinfunction "2_2") (pintype "passive"))
    )
    (net (code "94") (name "Net-(IC101-LOUT)") (class "Default")
      (node (ref "C108") (pin "+") (pinfunction "+_+") (pintype "passive"))
      (node (ref "IC101") (pin "28") (pinfunction "LOUT_28") (pintype "passive"))
    )
    (net (code "95") (name "Net-(IC101-MID)") (class "Default")
      (node (ref "C103") (pin "+") (pinfunction "+_+") (pintype "passive"))
      (node (ref "IC101") (pin "3") (pinfunction "MID_3") (pintype "passive"))
    )
    (net (code "96") (name "Net-(IC101-REFP)") (class "Default")
      (node (ref "C106") (pin "+") (pinfunction "+_+") (pintype "passive"))
      (node (ref "IC101") (pin "26") (pinfunction "REFP_26") (pintype "passive"))
      (node (ref "R104") (pin "1") (pinfunction "1_1") (pintype "passive"))
    )
    (net (code "97") (name "Net-(IC101-X1)") (class "Default")
      (node (ref "IC101") (pin "10") (pinfunction "X1_10") (pintype "passive"))
      (node (ref "Y100") (pin "2") (pinfunction "2_2") (pintype "passive"))
    )
    (net (code "98") (name "Net-(IC101-X2)") (class "Default")
      (node (ref "C104") (pin "1") (pinfunction "1_1") (pintype "passive"))
      (node (ref "IC101") (pin "9") (pinfunction "X2_9") (pintype "passive"))
      (node (ref "Y100") (pin "1") (pinfunction "1_1") (pintype "passive"))
    )
    (net (code "99") (name "Net-(K1A--)") (class "Default")
      (node (ref "D3") (pin "2") (pinfunction "2_2") (pintype "passive"))
      (node (ref "K1") (pin "8") (pinfunction "-_8") (pintype "passive"))
      (node (ref "Q1") (pin "3") (pinfunction "C_3") (pintype "passive"))
    )
    (net (code "100") (name "Net-(K1B-O)") (class "Default")
      (node (ref "K1") (pin "2") (pinfunction "O_2") (pintype "passive"))
      (node (ref "K1") (pin "7") (pinfunction "O_7") (pintype "passive"))
    )
    (net (code "101") (name "Net-(MIDI_IN-PadR)") (class "Default")
      (node (ref "MIDI_IN") (pin "R") (pinfunction "R_R") (pintype "passive"))
      (node (ref "R6") (pin "1") (pinfunction "1_1") (pintype "passive"))
    )
    (net (code "102") (name "Net-(MIDI_THRU-PadR)") (class "Default")
      (node (ref "MIDI_THRU") (pin "R") (pinfunction "R_R") (pintype "passive"))
      (node (ref "R9") (pin "1") (pinfunction "1_1") (pintype "passive"))
    )
    (net (code "103") (name "Net-(MIDI_THRU-PadT)") (class "Default")
      (node (ref "MIDI_THRU") (pin "T") (pinfunction "T_T") (pintype "passive"))
      (node (ref "R8") (pin "2") (pinfunction "2_2") (pintype "passive"))
    )
    (net (code "104") (name "Net-(OK1-A)") (class "Default")
      (node (ref "D2") (pin "1") (pinfunction "1_1") (pintype "passive"))
      (node (ref "OK1") (pin "1") (pinfunction "A_1") (pintype "passive"))
      (node (ref "R6") (pin "2") (pinfunction "2_2") (pintype "passive"))
    )
    (net (code "105") (name "Net-(OK1-K)") (class "Default")
      (node (ref "D2") (pin "2") (pinfunction "2_2") (pintype "passive"))
      (node (ref "MIDI_IN") (pin "T") (pinfunction "T_T") (pintype "passive"))
      (node (ref "OK1") (pin "3") (pinfunction "K_3") (pintype "passive"))
    )
    (net (code "106") (name "Net-(OK2-A)") (class "Default")
      (node (ref "OK2") (pin "1") (pinfunction "A_1") (pintype "passive"))
      (node (ref "R11") (pin "2") (pinfunction "2_2") (pintype "passive"))
    )
    (net (code "107") (name "Net-(PS_BRIGHT-Pad1)") (class "Default")
      (node (ref "PS_BRIGHT") (pin "1") (pinfunction "1_1") (pintype "passive"))
      (node (ref "R13") (pin "2") (pinfunction "2_2") (pintype "passive"))
    )
    (net (code "108") (name "Net-(Q1-B)") (class "Default")
      (node (ref "Q1") (pin "1") (pinfunction "B_1") (pintype "passive"))
      (node (ref "R12") (pin "2") (pinfunction "2_2") (pintype "passive"))
    )
    (net (code "109") (name "Net-(R15-Pad2)") (class "Default")
      (node (ref "R15") (pin "2") (pinfunction "2_2") (pintype "passive"))
      (node (ref "TAP_BRIGHT") (pin "1") (pinfunction "1_1") (pintype "passive"))
    )
    (net (code "110") (name "Net-(TAPLEDB-S)") (class "Default")
      (node (ref "TAPLED") (pin "1") (pinfunction "S_1") (pintype "passive"))
      (node (ref "TAP_BRIGHT") (pin "2") (pinfunction "2_2") (pintype "passive"))
      (node (ref "TAP_BRIGHT") (pin "3") (pinfunction "3_3") (pintype "passive"))
    )
    (net (code "111") (name "Vb") (class "Default")
      (node (ref "C116") (pin "+") (pinfunction "+_+") (pintype "passive"))
      (node (ref "IC100") (pin "10") (pinfunction "+IN_10") (pintype "passive"))
      (node (ref "IC100") (pin "5") (pinfunction "+IN_5") (pintype "passive"))
      (node (ref "IC6") (pin "4") (pinfunction "W_4") (pintype "passive"))
      (node (ref "R102") (pin "2") (pinfunction "2_2") (pintype "passive"))
      (node (ref "R106") (pin "2") (pinfunction "2_2") (pintype "passive"))
      (node (ref "R116") (pin "2") (pinfunction "2_2") (pintype "passive"))
      (node (ref "R117") (pin "2") (pinfunction "2_2") (pintype "passive"))
    )
    (net (code "112") (name "Vr") (class "Default")
      (node (ref "C115") (pin "+") (pinfunction "+_+") (pintype "passive"))
      (node (ref "C117") (pin "1") (pinfunction "1_1") (pintype "passive"))
      (node (ref "IC100") (pin "4") (pinfunction "V+_4") (pintype "power_in"))
      (node (ref "R115") (pin "2") (pinfunction "2_2") (pintype "passive"))
      (node (ref "R116") (pin "1") (pinfunction "1_1") (pintype "passive"))
    )
    (net (code "113") (name "unconnected-(IC2-NC-Pad1)") (class "Default")
      (node (ref "IC2") (pin "1") (pinfunction "NC_1") (pintype "passive"))
    )
    (net (code "114") (name "unconnected-(IC3-SDO-Pad22)") (class "Default")
      (node (ref "IC3") (pin "22") (pinfunction "SDO_22") (pintype "passive"))
    )
    (net (code "115") (name "unconnected-(IC5-SDO-Pad14)") (class "Default")
      (node (ref "IC5") (pin "14") (pinfunction "SDO_14") (pintype "passive"))
    )
    (net (code "116") (name "unconnected-(IC6-RDY-Pad14)") (class "Default")
      (node (ref "IC6") (pin "14") (pinfunction "RDY_14") (pintype "passive"))
    )
    (net (code "117") (name "unconnected-(IC6-SDO-Pad13)") (class "Default")
      (node (ref "IC6") (pin "13") (pinfunction "SDO_13") (pintype "passive"))
    )
    (net (code "118") (name "unconnected-(IC101-CLIP-Pad5)") (class "Default")
      (node (ref "IC101") (pin "5") (pinfunction "CLIP_5") (pintype "passive+no_connect"))
    )
    (net (code "119") (name "unconnected-(IC101-ROUT-Pad27)") (class "Default")
      (node (ref "IC101") (pin "27") (pinfunction "ROUT_27") (pintype "passive+no_connect"))
    )
    (net (code "120") (name "unconnected-(INPUT-PadR)") (class "Default")
      (node (ref "INPUT") (pin "R") (pinfunction "R_R") (pintype "passive+no_connect"))
    )
    (net (code "121") (name "unconnected-(INPUT-PadSN)") (class "Default")
      (node (ref "INPUT") (pin "SN") (pinfunction "SN_SN") (pintype "passive+no_connect"))
    )
    (net (code "122") (name "unconnected-(OUTPUT-PadR)") (class "Default")
      (node (ref "OUTPUT") (pin "R") (pinfunction "R_R") (pintype "passive+no_connect"))
    )
    (net (code "123") (name "unconnected-(OUTPUT-PadSN)") (class "Default")
      (node (ref "OUTPUT") (pin "SN") (pinfunction "SN_SN") (pintype "passive+no_connect"))
    )
    (net (code "124") (name "unconnected-(U1-PB0_(XCK0{slash}T0{slash}PCINT8)-Pad40)") (class "Default")
      (node (ref "U1") (pin "40") (pinfunction "PB0_(XCK0/T0/PCINT8)_40") (pintype "passive"))
    )
    (net (code "125") (name "unconnected-(U1-PB4_(SS{slash}OC0B{slash}PCINT12)-Pad44)") (class "Default")
      (node (ref "U1") (pin "44") (pinfunction "PB4_(SS/OC0B/PCINT12)_44") (pintype "passive"))
    )
    (net (code "126") (name "unconnected-(UART-Pad2)") (class "Default")
      (node (ref "UART") (pin "2") (pinfunction "2_2") (pintype "passive+no_connect"))
    )
  )
)
